# M843E.net
KiCad netlist of a schematic drawn in EAGLE
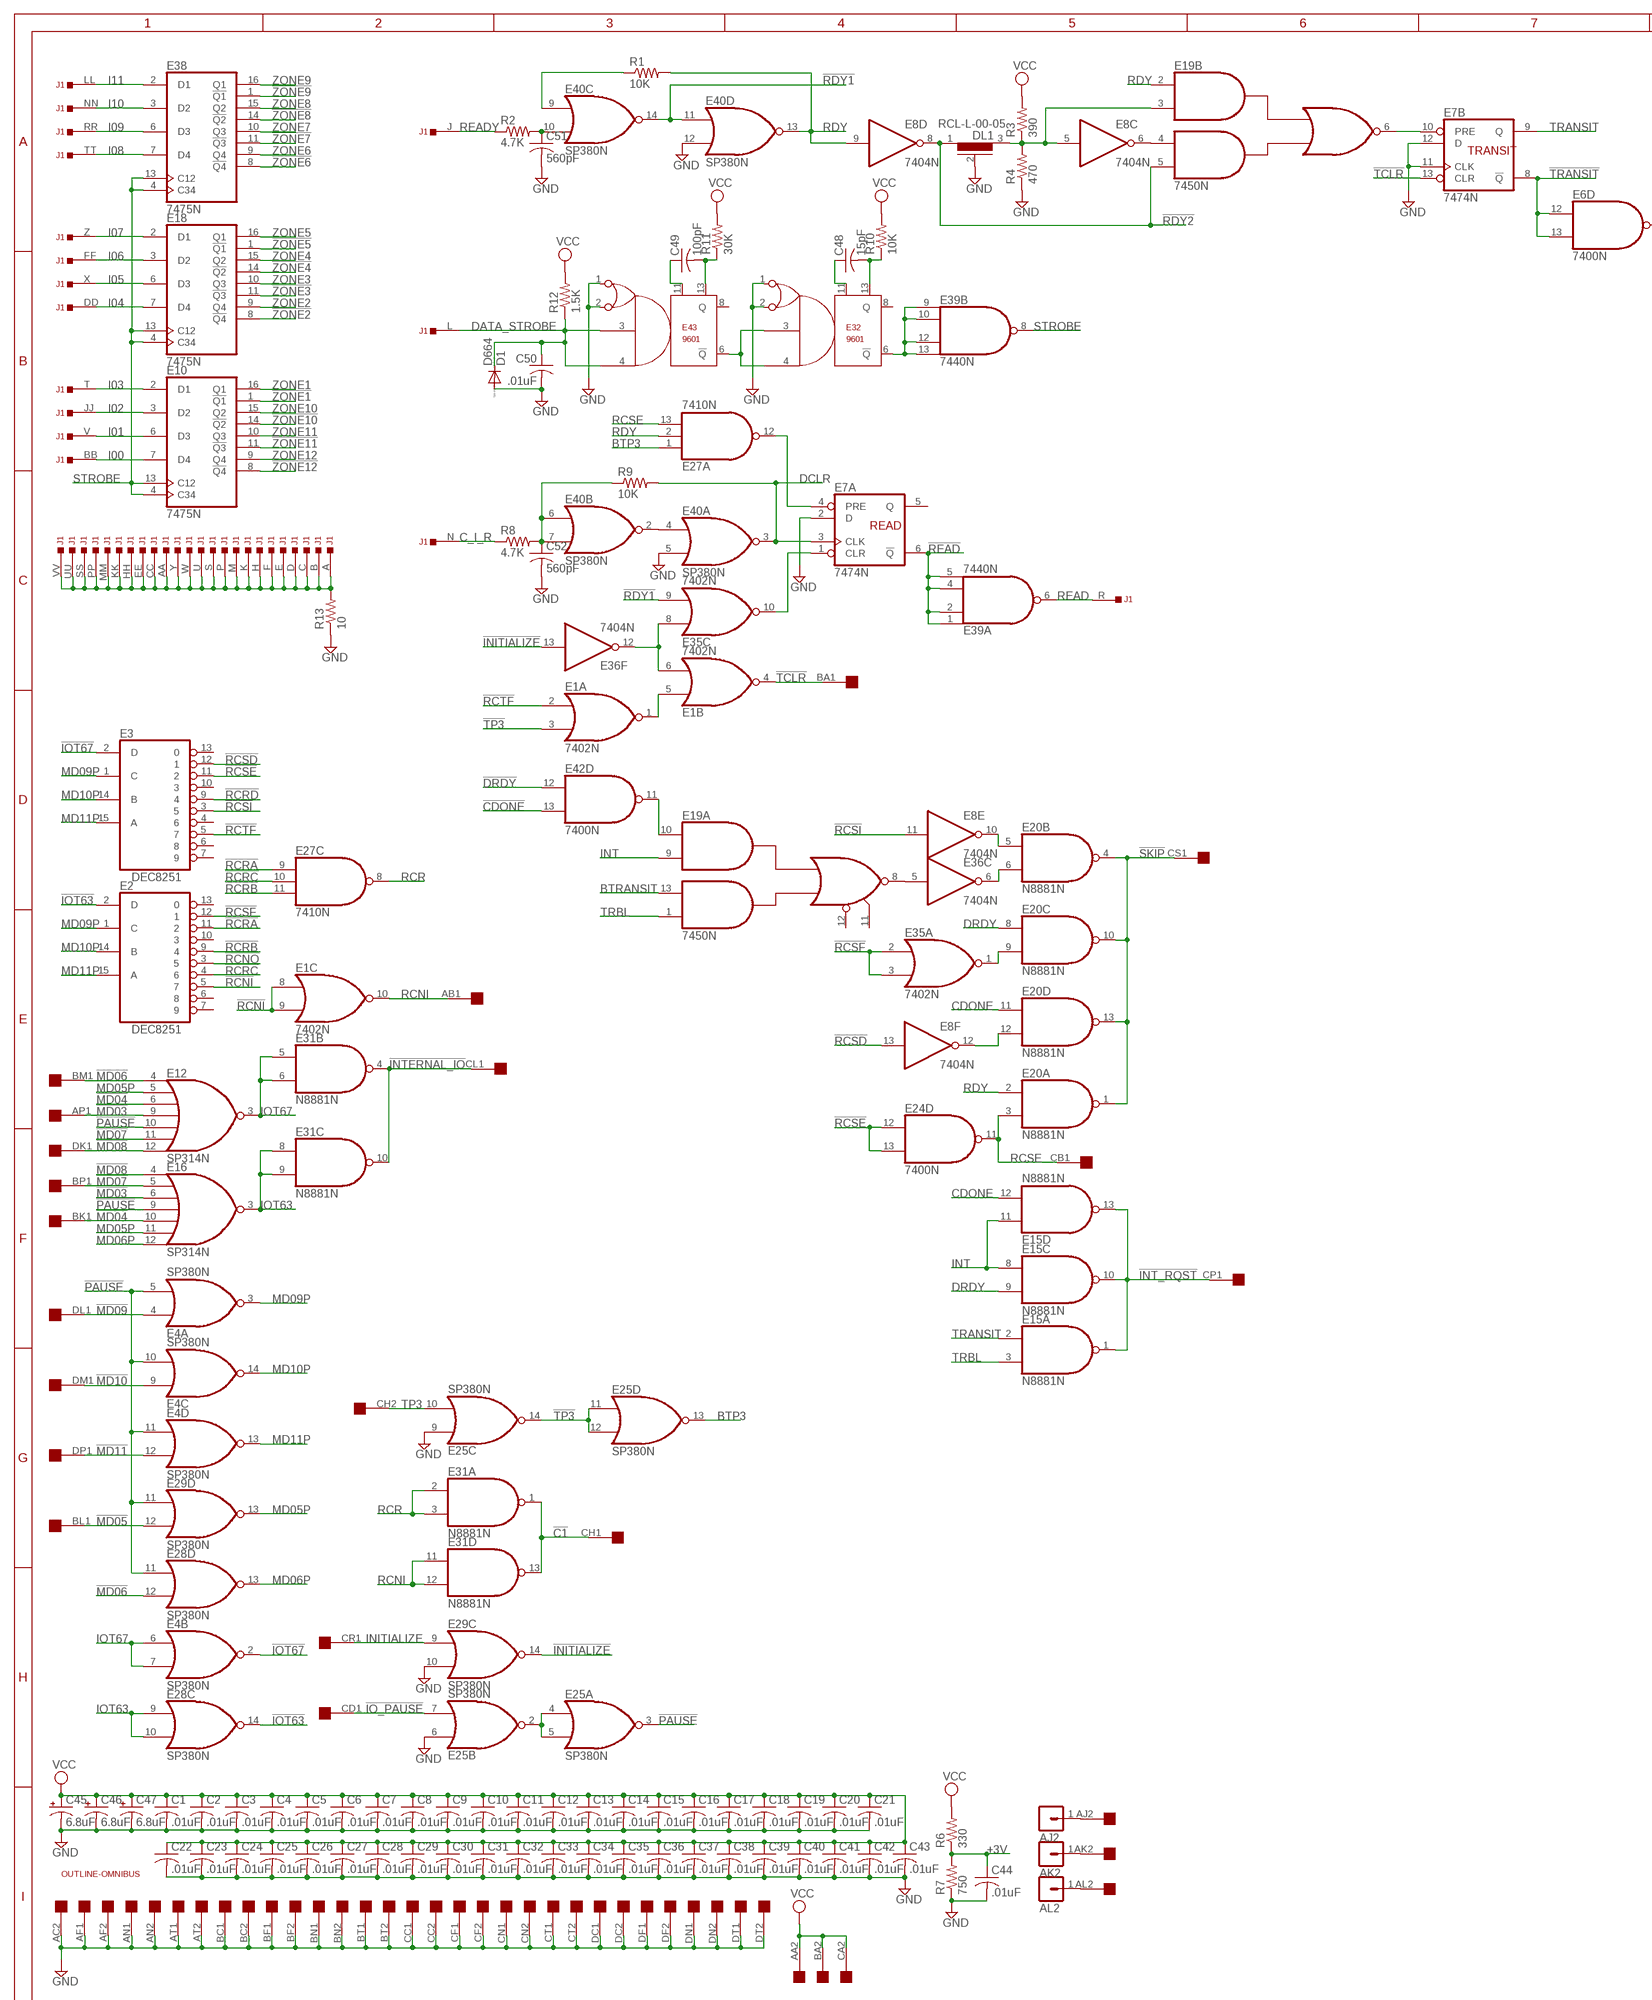
[diagram p0: schematic, sheet 1, part 1 of 2]
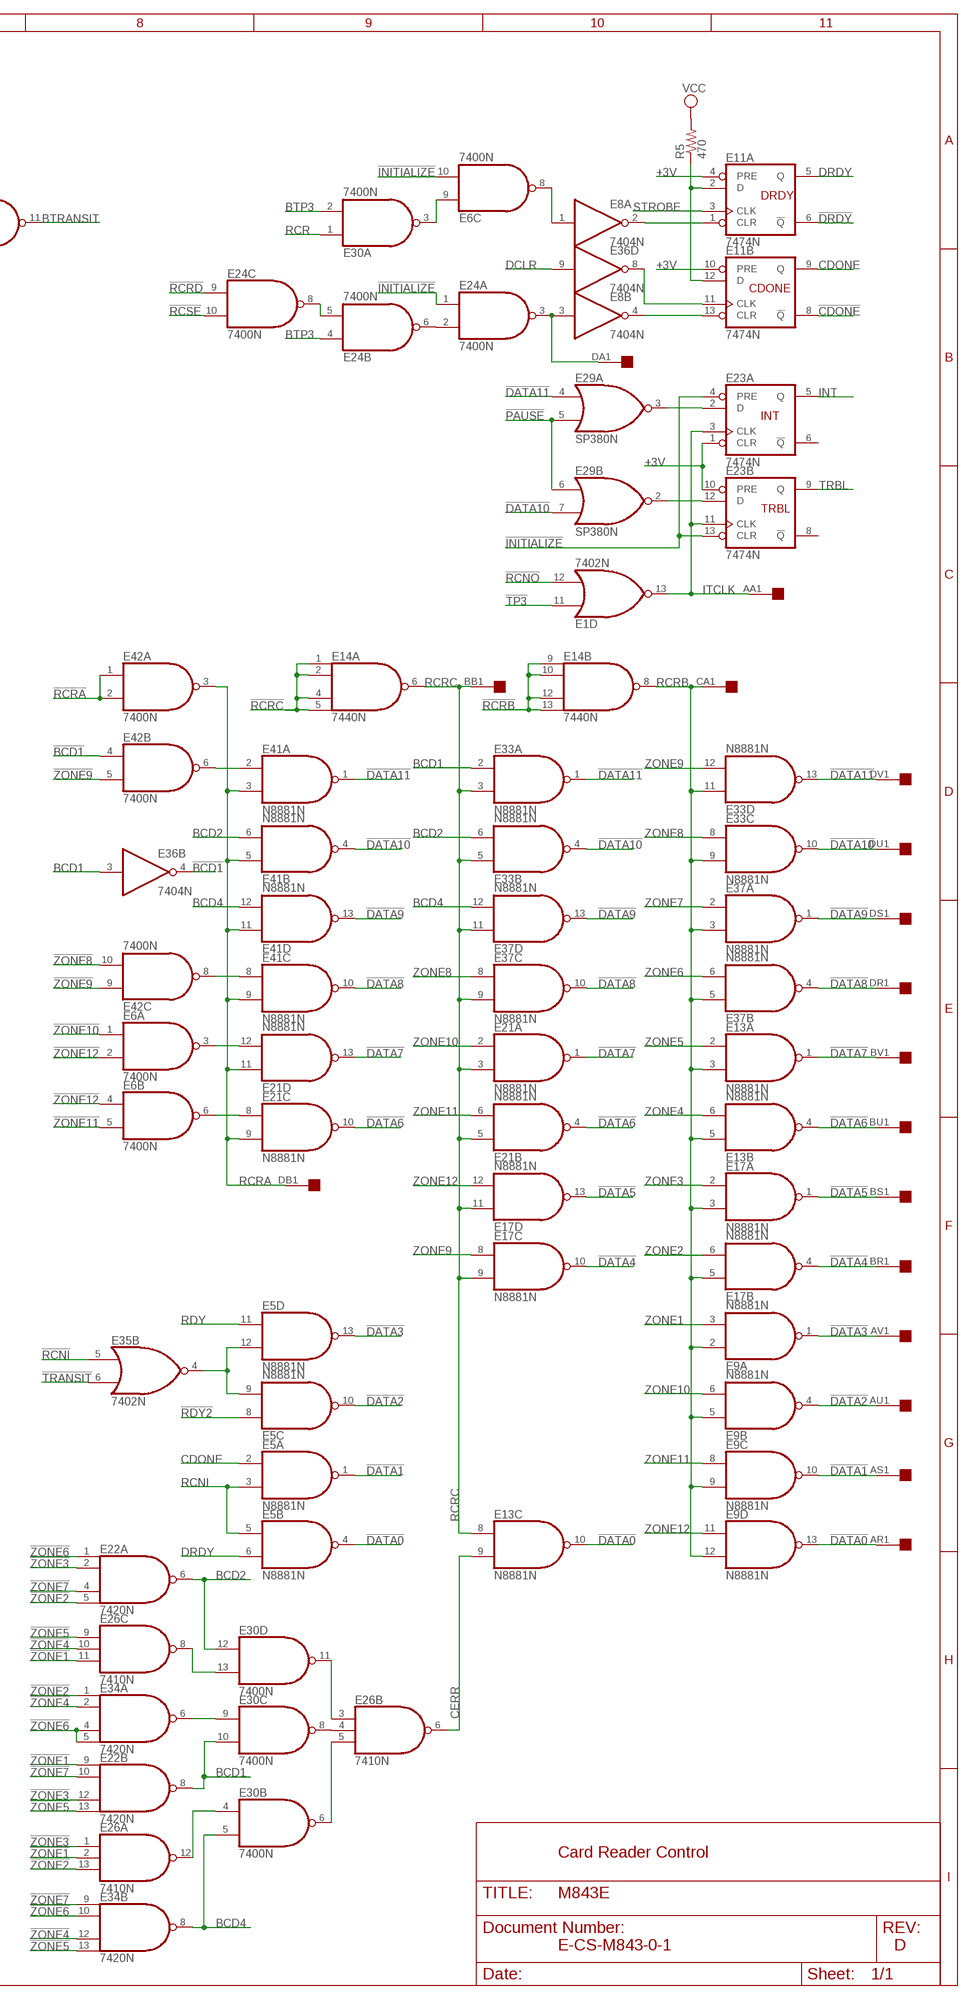
[diagram p1: schematic, sheet 1, part 2 of 2]

(export (version "E")
  (design (tool "Eeschema 10.0.6"))
  (components
    (comp (ref "AJ2")
      (value "MA01-1")
      (footprint "eagle-import:MA01-1")
      (libsource (lib "eagle-import") (part "MA01-1"))
    )
    (comp (ref "AK2")
      (value "MA01-1")
      (footprint "eagle-import:MA01-1")
      (libsource (lib "eagle-import") (part "MA01-1"))
    )
    (comp (ref "AL2")
      (value "MA01-1")
      (footprint "eagle-import:MA01-1")
      (libsource (lib "eagle-import") (part "MA01-1"))
    )
    (comp (ref "C1")
      (value ".01uF")
      (footprint "eagle-import:C075-032X103")
      (libsource (lib "eagle-import") (part "C-US075-032X103"))
    )
    (comp (ref "C2")
      (value ".01uF")
      (footprint "eagle-import:C063-025X075")
      (libsource (lib "eagle-import") (part "C-US"))
    )
    (comp (ref "C3")
      (value ".01uF")
      (footprint "eagle-import:C063-025X075")
      (libsource (lib "eagle-import") (part "C-US"))
    )
    (comp (ref "C4")
      (value ".01uF")
      (footprint "eagle-import:C063-025X075")
      (libsource (lib "eagle-import") (part "C-US"))
    )
    (comp (ref "C5")
      (value ".01uF")
      (footprint "eagle-import:C063-025X075")
      (libsource (lib "eagle-import") (part "C-US"))
    )
    (comp (ref "C6")
      (value ".01uF")
      (footprint "eagle-import:C075-032X103")
      (libsource (lib "eagle-import") (part "C-US075-032X103"))
    )
    (comp (ref "C7")
      (value ".01uF")
      (footprint "eagle-import:C063-025X075")
      (libsource (lib "eagle-import") (part "C-US"))
    )
    (comp (ref "C8")
      (value ".01uF")
      (footprint "eagle-import:C063-025X075")
      (libsource (lib "eagle-import") (part "C-US"))
    )
    (comp (ref "C9")
      (value ".01uF")
      (footprint "eagle-import:C063-025X075")
      (libsource (lib "eagle-import") (part "C-US"))
    )
    (comp (ref "C10")
      (value ".01uF")
      (footprint "eagle-import:C063-025X075")
      (libsource (lib "eagle-import") (part "C-US"))
    )
    (comp (ref "C11")
      (value ".01uF")
      (footprint "eagle-import:C063-025X075")
      (libsource (lib "eagle-import") (part "C-US"))
    )
    (comp (ref "C12")
      (value ".01uF")
      (footprint "eagle-import:C063-025X075")
      (libsource (lib "eagle-import") (part "C-US"))
    )
    (comp (ref "C13")
      (value ".01uF")
      (footprint "eagle-import:C063-025X075")
      (libsource (lib "eagle-import") (part "C-US"))
    )
    (comp (ref "C14")
      (value ".01uF")
      (footprint "eagle-import:C063-025X075")
      (libsource (lib "eagle-import") (part "C-US"))
    )
    (comp (ref "C15")
      (value ".01uF")
      (footprint "eagle-import:C063-025X075")
      (libsource (lib "eagle-import") (part "C-US"))
    )
    (comp (ref "C16")
      (value ".01uF")
      (footprint "eagle-import:C063-025X075")
      (libsource (lib "eagle-import") (part "C-US"))
    )
    (comp (ref "C17")
      (value ".01uF")
      (footprint "eagle-import:C063-025X075")
      (libsource (lib "eagle-import") (part "C-US"))
    )
    (comp (ref "C18")
      (value ".01uF")
      (footprint "eagle-import:C063-025X075")
      (libsource (lib "eagle-import") (part "C-US"))
    )
    (comp (ref "C19")
      (value ".01uF")
      (footprint "eagle-import:C063-025X075")
      (libsource (lib "eagle-import") (part "C-US"))
    )
    (comp (ref "C20")
      (value ".01uF")
      (footprint "eagle-import:C063-025X075")
      (libsource (lib "eagle-import") (part "C-US"))
    )
    (comp (ref "C21")
      (value ".01uF")
      (footprint "eagle-import:C063-025X075")
      (libsource (lib "eagle-import") (part "C-US"))
    )
    (comp (ref "C22")
      (value ".01uF")
      (footprint "eagle-import:C063-025X075")
      (libsource (lib "eagle-import") (part "C-US"))
    )
    (comp (ref "C23")
      (value ".01uF")
      (footprint "eagle-import:C063-025X075")
      (libsource (lib "eagle-import") (part "C-US"))
    )
    (comp (ref "C24")
      (value ".01uF")
      (footprint "eagle-import:C063-025X075")
      (libsource (lib "eagle-import") (part "C-US"))
    )
    (comp (ref "C25")
      (value ".01uF")
      (footprint "eagle-import:C063-025X075")
      (libsource (lib "eagle-import") (part "C-US"))
    )
    (comp (ref "C26")
      (value ".01uF")
      (footprint "eagle-import:C063-025X075")
      (libsource (lib "eagle-import") (part "C-US"))
    )
    (comp (ref "C27")
      (value ".01uF")
      (footprint "eagle-import:C063-025X075")
      (libsource (lib "eagle-import") (part "C-US"))
    )
    (comp (ref "C28")
      (value ".01uF")
      (footprint "eagle-import:C063-025X075")
      (libsource (lib "eagle-import") (part "C-US"))
    )
    (comp (ref "C29")
      (value ".01uF")
      (footprint "eagle-import:C063-025X075")
      (libsource (lib "eagle-import") (part "C-US"))
    )
    (comp (ref "C30")
      (value ".01uF")
      (footprint "eagle-import:C063-025X075")
      (libsource (lib "eagle-import") (part "C-US"))
    )
    (comp (ref "C31")
      (value ".01uF")
      (footprint "eagle-import:C063-025X075")
      (libsource (lib "eagle-import") (part "C-US"))
    )
    (comp (ref "C32")
      (value ".01uF")
      (footprint "eagle-import:C063-025X075")
      (libsource (lib "eagle-import") (part "C-US"))
    )
    (comp (ref "C33")
      (value ".01uF")
      (footprint "eagle-import:C063-025X075")
      (libsource (lib "eagle-import") (part "C-US"))
    )
    (comp (ref "C34")
      (value ".01uF")
      (footprint "eagle-import:C063-025X075")
      (libsource (lib "eagle-import") (part "C-US"))
    )
    (comp (ref "C35")
      (value ".01uF")
      (footprint "eagle-import:C063-025X075")
      (libsource (lib "eagle-import") (part "C-US"))
    )
    (comp (ref "C36")
      (value ".01uF")
      (footprint "eagle-import:C063-025X075")
      (libsource (lib "eagle-import") (part "C-US"))
    )
    (comp (ref "C37")
      (value ".01uF")
      (footprint "eagle-import:C063-025X075")
      (libsource (lib "eagle-import") (part "C-US"))
    )
    (comp (ref "C38")
      (value ".01uF")
      (footprint "eagle-import:C063-025X075")
      (libsource (lib "eagle-import") (part "C-US"))
    )
    (comp (ref "C39")
      (value ".01uF")
      (footprint "eagle-import:C063-025X075")
      (libsource (lib "eagle-import") (part "C-US"))
    )
    (comp (ref "C40")
      (value ".01uF")
      (footprint "eagle-import:C063-025X075")
      (libsource (lib "eagle-import") (part "C-US"))
    )
    (comp (ref "C41")
      (value ".01uF")
      (footprint "eagle-import:C063-025X075")
      (libsource (lib "eagle-import") (part "C-US"))
    )
    (comp (ref "C42")
      (value ".01uF")
      (footprint "eagle-import:C063-025X075")
      (libsource (lib "eagle-import") (part "C-US"))
    )
    (comp (ref "C43")
      (value ".01uF")
      (footprint "eagle-import:C063-025X075")
      (libsource (lib "eagle-import") (part "C-US"))
    )
    (comp (ref "C44")
      (value ".01uF")
      (footprint "eagle-import:C063-025X075")
      (libsource (lib "eagle-import") (part "C-US"))
    )
    (comp (ref "C45")
      (value "6.8uF")
      (footprint "eagle-import:E12-8")
      (libsource (lib "eagle-import") (part "CPOL-USE20-8AXIAL"))
    )
    (comp (ref "C46")
      (value "6.8uF")
      (footprint "eagle-import:E12-8")
      (libsource (lib "eagle-import") (part "CPOL-USE20-8AXIAL"))
    )
    (comp (ref "C47")
      (value "6.8uF")
      (footprint "eagle-import:E12-8")
      (libsource (lib "eagle-import") (part "CPOL-USE20-8AXIAL"))
    )
    (comp (ref "C48")
      (value "15pF")
      (footprint "eagle-import:C075-032X103")
      (libsource (lib "eagle-import") (part "C-US075-032X103"))
    )
    (comp (ref "C49")
      (value "100pF")
      (footprint "eagle-import:C075-032X103")
      (libsource (lib "eagle-import") (part "C-US075-032X103"))
    )
    (comp (ref "C50")
      (value ".01uF")
      (footprint "eagle-import:C063-025X075")
      (libsource (lib "eagle-import") (part "C-US"))
    )
    (comp (ref "C51")
      (value "560pF")
      (footprint "eagle-import:C075-032X103")
      (libsource (lib "eagle-import") (part "C-US075-032X103"))
    )
    (comp (ref "C52")
      (value "560pF")
      (footprint "eagle-import:C075-032X103")
      (libsource (lib "eagle-import") (part "C-US075-032X103"))
    )
    (comp (ref "D1")
      (value "D664")
      (footprint "eagle-import:DO35-10")
      (libsource (lib "eagle-import") (part "DIODE-DO35-10"))
    )
    (comp (ref "DL1")
      (value "RCL-L-00-05")
      (footprint "eagle-import:RCL-L-00-05")
      (libsource (lib "eagle-import") (part "RCL-L-00-05"))
    )
    (comp (ref "E1")
      (value "7402N")
      (footprint "eagle-import:DIL14")
      (libsource (lib "eagle-import") (part "7402N"))
    )
    (comp (ref "E2")
      (value "DEC8251")
      (footprint "eagle-import:DIL16")
      (libsource (lib "eagle-import") (part "DEC8251"))
    )
    (comp (ref "E3")
      (value "DEC8251")
      (footprint "eagle-import:DIL16")
      (libsource (lib "eagle-import") (part "DEC8251"))
    )
    (comp (ref "E4")
      (value "SP380N")
      (footprint "eagle-import:DIL14")
      (libsource (lib "eagle-import") (part "SP380N"))
    )
    (comp (ref "E5")
      (value "N8881N")
      (footprint "eagle-import:DIL14")
      (libsource (lib "eagle-import") (part "N8881N"))
    )
    (comp (ref "E6")
      (value "7400N")
      (footprint "eagle-import:DIL14")
      (libsource (lib "eagle-import") (part "7400N"))
    )
    (comp (ref "E7")
      (value "7474N")
      (footprint "eagle-import:DIL14")
      (libsource (lib "eagle-import") (part "7474NS"))
    )
    (comp (ref "E8")
      (value "7404N")
      (footprint "eagle-import:DIL14")
      (libsource (lib "eagle-import") (part "7404N"))
    )
    (comp (ref "E9")
      (value "N8881N")
      (footprint "eagle-import:DIL14")
      (libsource (lib "eagle-import") (part "N8881N"))
    )
    (comp (ref "E10")
      (value "7475N")
      (footprint "eagle-import:DIL16")
      (libsource (lib "eagle-import") (part "7475N"))
    )
    (comp (ref "E11")
      (value "7474N")
      (footprint "eagle-import:DIL14")
      (libsource (lib "eagle-import") (part "7474NS"))
    )
    (comp (ref "E12")
      (value "SP314N")
      (footprint "eagle-import:DIL14")
      (libsource (lib "eagle-import") (part "SP314N"))
    )
    (comp (ref "E13")
      (value "N8881N")
      (footprint "eagle-import:DIL14")
      (libsource (lib "eagle-import") (part "N8881N"))
    )
    (comp (ref "E14")
      (value "7440N")
      (footprint "eagle-import:DIL14")
      (libsource (lib "eagle-import") (part "7440N"))
    )
    (comp (ref "E15")
      (value "N8881N")
      (footprint "eagle-import:DIL14")
      (libsource (lib "eagle-import") (part "N8881N"))
    )
    (comp (ref "E16")
      (value "SP314N")
      (footprint "eagle-import:DIL14")
      (libsource (lib "eagle-import") (part "SP314N"))
    )
    (comp (ref "E17")
      (value "N8881N")
      (footprint "eagle-import:DIL14")
      (libsource (lib "eagle-import") (part "N8881N"))
    )
    (comp (ref "E18")
      (value "7475N")
      (footprint "eagle-import:DIL16")
      (libsource (lib "eagle-import") (part "7475N"))
    )
    (comp (ref "E19")
      (value "7450N")
      (footprint "eagle-import:DIL14")
      (libsource (lib "eagle-import") (part "7450N"))
    )
    (comp (ref "E20")
      (value "N8881N")
      (footprint "eagle-import:DIL14")
      (libsource (lib "eagle-import") (part "N8881N"))
    )
    (comp (ref "E21")
      (value "N8881N")
      (footprint "eagle-import:DIL14")
      (libsource (lib "eagle-import") (part "N8881N"))
    )
    (comp (ref "E22")
      (value "7420N")
      (footprint "eagle-import:DIL14")
      (libsource (lib "eagle-import") (part "7420N"))
    )
    (comp (ref "E23")
      (value "7474N")
      (footprint "eagle-import:DIL14")
      (libsource (lib "eagle-import") (part "7474NS"))
    )
    (comp (ref "E24")
      (value "7400N")
      (footprint "eagle-import:DIL14")
      (libsource (lib "eagle-import") (part "7400N"))
    )
    (comp (ref "E25")
      (value "SP380N")
      (footprint "eagle-import:DIL14")
      (libsource (lib "eagle-import") (part "SP380N"))
    )
    (comp (ref "E26")
      (value "7410N")
      (footprint "eagle-import:DIL14")
      (libsource (lib "eagle-import") (part "7410N"))
    )
    (comp (ref "E27")
      (value "7410N")
      (footprint "eagle-import:DIL14")
      (libsource (lib "eagle-import") (part "7410N"))
    )
    (comp (ref "E28")
      (value "SP380N")
      (footprint "eagle-import:DIL14")
      (libsource (lib "eagle-import") (part "SP380N"))
    )
    (comp (ref "E29")
      (value "SP380N")
      (footprint "eagle-import:DIL14")
      (libsource (lib "eagle-import") (part "SP380N"))
    )
    (comp (ref "E30")
      (value "7400N")
      (footprint "eagle-import:DIL14")
      (libsource (lib "eagle-import") (part "7400N"))
    )
    (comp (ref "E31")
      (value "N8881N")
      (footprint "eagle-import:DIL14")
      (libsource (lib "eagle-import") (part "N8881N"))
    )
    (comp (ref "E32")
      (value "9601")
      (footprint "eagle-import:DIL14")
      (libsource (lib "eagle-import") (part "9601"))
    )
    (comp (ref "E33")
      (value "N8881N")
      (footprint "eagle-import:DIL14")
      (libsource (lib "eagle-import") (part "N8881N"))
    )
    (comp (ref "E34")
      (value "7420N")
      (footprint "eagle-import:DIL14")
      (libsource (lib "eagle-import") (part "7420N"))
    )
    (comp (ref "E35")
      (value "7402N")
      (footprint "eagle-import:DIL14")
      (libsource (lib "eagle-import") (part "7402N"))
    )
    (comp (ref "E36")
      (value "7404N")
      (footprint "eagle-import:DIL14")
      (libsource (lib "eagle-import") (part "7404N"))
    )
    (comp (ref "E37")
      (value "N8881N")
      (footprint "eagle-import:DIL14")
      (libsource (lib "eagle-import") (part "N8881N"))
    )
    (comp (ref "E38")
      (value "7475N")
      (footprint "eagle-import:DIL16")
      (libsource (lib "eagle-import") (part "7475N"))
    )
    (comp (ref "E39")
      (value "7440N")
      (footprint "eagle-import:DIL14")
      (libsource (lib "eagle-import") (part "7440N"))
    )
    (comp (ref "E40")
      (value "SP380N")
      (footprint "eagle-import:DIL14")
      (libsource (lib "eagle-import") (part "SP380N"))
    )
    (comp (ref "E41")
      (value "N8881N")
      (footprint "eagle-import:DIL14")
      (libsource (lib "eagle-import") (part "N8881N"))
    )
    (comp (ref "E42")
      (value "7400N")
      (footprint "eagle-import:DIL14")
      (libsource (lib "eagle-import") (part "7400N"))
    )
    (comp (ref "E43")
      (value "9601")
      (footprint "eagle-import:DIL14")
      (libsource (lib "eagle-import") (part "9601"))
    )
    (comp (ref "EDGE")
      (value "OMNIBUS")
      (footprint "eagle-import:EDGE-CON8")
      (libsource (lib "eagle-import") (part "QUAD"))
    )
    (comp (ref "J1")
      (value "DEC40PINSH")
      (footprint "eagle-import:DEC40PINH")
      (libsource (lib "eagle-import") (part "DEC40PINSH"))
    )
    (comp (ref "R1")
      (value "10K")
      (footprint "eagle-import:0207_10")
      (libsource (lib "eagle-import") (part "R-US_0207/10"))
    )
    (comp (ref "R2")
      (value "4.7K")
      (footprint "eagle-import:0207_10")
      (libsource (lib "eagle-import") (part "R-US_0207/10"))
    )
    (comp (ref "R3")
      (value "390")
      (footprint "eagle-import:0207_10")
      (libsource (lib "eagle-import") (part "R-US_0207/10"))
    )
    (comp (ref "R4")
      (value "470")
      (footprint "eagle-import:0207_10")
      (libsource (lib "eagle-import") (part "R-US_0207/10"))
    )
    (comp (ref "R5")
      (value "470")
      (footprint "eagle-import:0207_10")
      (libsource (lib "eagle-import") (part "R-US_0207/10"))
    )
    (comp (ref "R6")
      (value "330")
      (footprint "eagle-import:0207_10")
      (libsource (lib "eagle-import") (part "R-US_0207/10"))
    )
    (comp (ref "R7")
      (value "750")
      (footprint "eagle-import:0207_10")
      (libsource (lib "eagle-import") (part "R-US_0207/10"))
    )
    (comp (ref "R8")
      (value "4.7K")
      (footprint "eagle-import:0207_10")
      (libsource (lib "eagle-import") (part "R-US_0207/10"))
    )
    (comp (ref "R9")
      (value "10K")
      (footprint "eagle-import:0207_10")
      (libsource (lib "eagle-import") (part "R-US_0207/10"))
    )
    (comp (ref "R10")
      (value "10K")
      (footprint "eagle-import:0207_10")
      (libsource (lib "eagle-import") (part "R-US_0207/10"))
    )
    (comp (ref "R11")
      (value "30K")
      (footprint "eagle-import:0207_10")
      (libsource (lib "eagle-import") (part "R-US_0207/10"))
    )
    (comp (ref "R12")
      (value "1.5K")
      (footprint "eagle-import:0207_10")
      (libsource (lib "eagle-import") (part "R-US_0207/10"))
    )
    (comp (ref "R13")
      (value "10")
      (footprint "eagle-import:0207_10")
      (libsource (lib "eagle-import") (part "R-US_0207/10"))
    )
    (comp (ref "U$4")
      (value "OUTLINE-OMNIBUS")
      (footprint "eagle-import:OMNIBUS")
      (libsource (lib "eagle-import") (part "OUTLINE-OMNIBUS"))
    )
  )
  (nets
    (net (code "1") (name "/+3V") (class "Default")
      (node (ref "C44") (pin "1") (pinfunction "1_1") (pintype "passive"))
      (node (ref "E11") (pin "10") (pinfunction "PRE_10") (pintype "input"))
      (node (ref "E11") (pin "4") (pinfunction "PRE_4") (pintype "input"))
      (node (ref "E23") (pin "1") (pinfunction "CLR_1") (pintype "input"))
      (node (ref "E23") (pin "10") (pinfunction "PRE_10") (pintype "input"))
      (node (ref "R6") (pin "1") (pinfunction "1_1") (pintype "passive"))
      (node (ref "R7") (pin "2") (pinfunction "2_2") (pintype "passive"))
    )
    (net (code "2") (name "/BCD1") (class "Default")
      (node (ref "E22") (pin "8") (pinfunction "O_8") (pintype "output"))
      (node (ref "E30") (pin "10") (pinfunction "I1_10") (pintype "input"))
      (node (ref "E33") (pin "2") (pinfunction "I0_2") (pintype "input"))
      (node (ref "E36") (pin "3") (pinfunction "I_3") (pintype "input"))
    )
    (net (code "3") (name "/BCD2") (class "Default")
      (node (ref "E22") (pin "6") (pinfunction "O_6") (pintype "output"))
      (node (ref "E30") (pin "12") (pinfunction "I0_12") (pintype "input"))
      (node (ref "E33") (pin "6") (pinfunction "I1_6") (pintype "input"))
      (node (ref "E41") (pin "6") (pinfunction "I1_6") (pintype "input"))
    )
    (net (code "4") (name "/BCD4") (class "Default")
      (node (ref "E30") (pin "5") (pinfunction "I1_5") (pintype "input"))
      (node (ref "E34") (pin "8") (pinfunction "O_8") (pintype "output"))
      (node (ref "E37") (pin "12") (pinfunction "I1_12") (pintype "input"))
      (node (ref "E41") (pin "12") (pinfunction "I1_12") (pintype "input"))
    )
    (net (code "5") (name "/BTP3") (class "Default")
      (node (ref "E24") (pin "4") (pinfunction "I0_4") (pintype "input"))
      (node (ref "E25") (pin "13") (pinfunction "O_13") (pintype "output"))
      (node (ref "E27") (pin "1") (pinfunction "I0_1") (pintype "input"))
      (node (ref "E30") (pin "2") (pinfunction "I1_2") (pintype "input"))
    )
    (net (code "6") (name "/BTRANSIT") (class "Default")
      (node (ref "E19") (pin "13") (pinfunction "I3_13") (pintype "input"))
      (node (ref "E6") (pin "11") (pinfunction "O_11") (pintype "output"))
    )
    (net (code "7") (name "/CDONE") (class "Default")
      (node (ref "E11") (pin "9") (pinfunction "Q_9") (pintype "output"))
      (node (ref "E15") (pin "12") (pinfunction "I1_12") (pintype "input"))
      (node (ref "E20") (pin "11") (pinfunction "I0_11") (pintype "input"))
      (node (ref "E5") (pin "2") (pinfunction "I0_2") (pintype "input"))
    )
    (net (code "8") (name "/CERR") (class "Default")
      (node (ref "E13") (pin "9") (pinfunction "I1_9") (pintype "input"))
      (node (ref "E26") (pin "6") (pinfunction "O_6") (pintype "output"))
    )
    (net (code "9") (name "/C_I_R") (class "Default")
      (node (ref "J1") (pin "N") (pinfunction "P_N") (pintype "passive"))
      (node (ref "R8") (pin "1") (pinfunction "1_1") (pintype "passive"))
    )
    (net (code "10") (name "/DATA_STROBE") (class "Default")
      (node (ref "C50") (pin "1") (pinfunction "1_1") (pintype "passive"))
      (node (ref "D1") (pin "C") (pinfunction "C_C") (pintype "passive"))
      (node (ref "E43") (pin "3") (pinfunction "P$3_3") (pintype "input"))
      (node (ref "E43") (pin "4") (pinfunction "P$4_4") (pintype "input"))
      (node (ref "J1") (pin "L") (pinfunction "P_L") (pintype "passive"))
      (node (ref "R12") (pin "1") (pinfunction "1_1") (pintype "passive"))
    )
    (net (code "11") (name "/DCLR") (class "Default")
      (node (ref "E36") (pin "9") (pinfunction "I_9") (pintype "input"))
      (node (ref "E40") (pin "3") (pinfunction "O_3") (pintype "output"))
      (node (ref "E7") (pin "3") (pinfunction "CLK_3") (pintype "input"))
      (node (ref "R9") (pin "2") (pinfunction "2_2") (pintype "passive"))
    )
    (net (code "12") (name "/DRDY") (class "Default")
      (node (ref "E11") (pin "5") (pinfunction "Q_5") (pintype "output"))
      (node (ref "E15") (pin "9") (pinfunction "I1_9") (pintype "input"))
      (node (ref "E20") (pin "8") (pinfunction "I0_8") (pintype "input"))
      (node (ref "E5") (pin "6") (pinfunction "I1_6") (pintype "input"))
    )
    (net (code "13") (name "/I00") (class "Default")
      (node (ref "E10") (pin "7") (pinfunction "D4_7") (pintype "input"))
      (node (ref "J1") (pin "BB") (pinfunction "P_BB") (pintype "passive"))
    )
    (net (code "14") (name "/I01") (class "Default")
      (node (ref "E10") (pin "6") (pinfunction "D3_6") (pintype "input"))
      (node (ref "J1") (pin "V") (pinfunction "P_V") (pintype "passive"))
    )
    (net (code "15") (name "/I02") (class "Default")
      (node (ref "E10") (pin "3") (pinfunction "D2_3") (pintype "input"))
      (node (ref "J1") (pin "JJ") (pinfunction "P_JJ") (pintype "passive"))
    )
    (net (code "16") (name "/I03") (class "Default")
      (node (ref "E10") (pin "2") (pinfunction "D1_2") (pintype "input"))
      (node (ref "J1") (pin "T") (pinfunction "P_T") (pintype "passive"))
    )
    (net (code "17") (name "/I04") (class "Default")
      (node (ref "E18") (pin "7") (pinfunction "D4_7") (pintype "input"))
      (node (ref "J1") (pin "DD") (pinfunction "P_DD") (pintype "passive"))
    )
    (net (code "18") (name "/I05") (class "Default")
      (node (ref "E18") (pin "6") (pinfunction "D3_6") (pintype "input"))
      (node (ref "J1") (pin "X") (pinfunction "P_X") (pintype "passive"))
    )
    (net (code "19") (name "/I06") (class "Default")
      (node (ref "E18") (pin "3") (pinfunction "D2_3") (pintype "input"))
      (node (ref "J1") (pin "FF") (pinfunction "P_FF") (pintype "passive"))
    )
    (net (code "20") (name "/I07") (class "Default")
      (node (ref "E18") (pin "2") (pinfunction "D1_2") (pintype "input"))
      (node (ref "J1") (pin "Z") (pinfunction "P_Z") (pintype "passive"))
    )
    (net (code "21") (name "/I08") (class "Default")
      (node (ref "E38") (pin "7") (pinfunction "D4_7") (pintype "input"))
      (node (ref "J1") (pin "TT") (pinfunction "P_TT") (pintype "passive"))
    )
    (net (code "22") (name "/I09") (class "Default")
      (node (ref "E38") (pin "6") (pinfunction "D3_6") (pintype "input"))
      (node (ref "J1") (pin "RR") (pinfunction "P_RR") (pintype "passive"))
    )
    (net (code "23") (name "/I10") (class "Default")
      (node (ref "E38") (pin "3") (pinfunction "D2_3") (pintype "input"))
      (node (ref "J1") (pin "NN") (pinfunction "P_NN") (pintype "passive"))
    )
    (net (code "24") (name "/I11") (class "Default")
      (node (ref "E38") (pin "2") (pinfunction "D1_2") (pintype "input"))
      (node (ref "J1") (pin "LL") (pinfunction "P_LL") (pintype "passive"))
    )
    (net (code "25") (name "/INITIALIZE") (class "Default")
      (node (ref "E29") (pin "9") (pinfunction "I0_9") (pintype "input"))
      (node (ref "EDGE") (pin "CR1") (pinfunction "1_CR1") (pintype "bidirectional"))
    )
    (net (code "26") (name "/INT") (class "Default")
      (node (ref "E15") (pin "11") (pinfunction "I0_11") (pintype "input"))
      (node (ref "E15") (pin "8") (pinfunction "I0_8") (pintype "input"))
      (node (ref "E19") (pin "9") (pinfunction "I2_9") (pintype "input"))
      (node (ref "E23") (pin "5") (pinfunction "Q_5") (pintype "output"))
    )
    (net (code "27") (name "/IOT63") (class "Default")
      (node (ref "E16") (pin "3") (pinfunction "O_3") (pintype "output"))
      (node (ref "E28") (pin "10") (pinfunction "I1_10") (pintype "input"))
      (node (ref "E28") (pin "9") (pinfunction "I0_9") (pintype "input"))
      (node (ref "E31") (pin "8") (pinfunction "I0_8") (pintype "input"))
      (node (ref "E31") (pin "9") (pinfunction "I1_9") (pintype "input"))
    )
    (net (code "28") (name "/IOT67") (class "Default")
      (node (ref "E12") (pin "3") (pinfunction "O_3") (pintype "output"))
      (node (ref "E31") (pin "5") (pinfunction "I0_5") (pintype "input"))
      (node (ref "E31") (pin "6") (pinfunction "I1_6") (pintype "input"))
      (node (ref "E4") (pin "6") (pinfunction "I0_6") (pintype "input"))
      (node (ref "E4") (pin "7") (pinfunction "I1_7") (pintype "input"))
    )
    (net (code "29") (name "/ITCLK") (class "Default")
      (node (ref "E1") (pin "13") (pinfunction "O_13") (pintype "output"))
      (node (ref "E23") (pin "11") (pinfunction "CLK_11") (pintype "input"))
      (node (ref "E23") (pin "3") (pinfunction "CLK_3") (pintype "input"))
      (node (ref "EDGE") (pin "AA1") (pinfunction "1_AA1") (pintype "bidirectional"))
    )
    (net (code "30") (name "/MD05P") (class "Default")
      (node (ref "E12") (pin "5") (pinfunction "I1_5") (pintype "input"))
      (node (ref "E16") (pin "11") (pinfunction "I5_11") (pintype "input"))
      (node (ref "E29") (pin "13") (pinfunction "O_13") (pintype "output"))
    )
    (net (code "31") (name "/MD06P") (class "Default")
      (node (ref "E16") (pin "12") (pinfunction "I6_12") (pintype "input"))
      (node (ref "E28") (pin "13") (pinfunction "O_13") (pintype "output"))
    )
    (net (code "32") (name "/MD09P") (class "Default")
      (node (ref "E2") (pin "1") (pinfunction "C_1") (pintype "input"))
      (node (ref "E3") (pin "1") (pinfunction "C_1") (pintype "input"))
      (node (ref "E4") (pin "3") (pinfunction "O_3") (pintype "output"))
    )
    (net (code "33") (name "/MD10P") (class "Default")
      (node (ref "E2") (pin "14") (pinfunction "B_14") (pintype "input"))
      (node (ref "E3") (pin "14") (pinfunction "B_14") (pintype "input"))
      (node (ref "E4") (pin "14") (pinfunction "O_14") (pintype "output"))
    )
    (net (code "34") (name "/MD11P") (class "Default")
      (node (ref "E2") (pin "15") (pinfunction "A_15") (pintype "input"))
      (node (ref "E3") (pin "15") (pinfunction "A_15") (pintype "input"))
      (node (ref "E4") (pin "13") (pinfunction "O_13") (pintype "output"))
    )
    (net (code "35") (name "/RCNI") (class "Default")
      (node (ref "E1") (pin "10") (pinfunction "O_10") (pintype "output"))
      (node (ref "E31") (pin "11") (pinfunction "I0_11") (pintype "input"))
      (node (ref "E31") (pin "12") (pinfunction "I1_12") (pintype "input"))
      (node (ref "E5") (pin "3") (pinfunction "I1_3") (pintype "input"))
      (node (ref "E5") (pin "5") (pinfunction "I0_5") (pintype "input"))
      (node (ref "EDGE") (pin "AB1") (pinfunction "1_AB1") (pintype "bidirectional"))
    )
    (net (code "36") (name "/RCR") (class "Default")
      (node (ref "E27") (pin "8") (pinfunction "O_8") (pintype "output"))
      (node (ref "E30") (pin "1") (pinfunction "I0_1") (pintype "input"))
      (node (ref "E31") (pin "2") (pinfunction "I0_2") (pintype "input"))
      (node (ref "E31") (pin "3") (pinfunction "I1_3") (pintype "input"))
    )
    (net (code "37") (name "/RCRA") (class "Default")
      (node (ref "E21") (pin "11") (pinfunction "I0_11") (pintype "input"))
      (node (ref "E21") (pin "9") (pinfunction "I1_9") (pintype "input"))
      (node (ref "E41") (pin "11") (pinfunction "I0_11") (pintype "input"))
      (node (ref "E41") (pin "3") (pinfunction "I1_3") (pintype "input"))
      (node (ref "E41") (pin "5") (pinfunction "I0_5") (pintype "input"))
      (node (ref "E41") (pin "9") (pinfunction "I1_9") (pintype "input"))
      (node (ref "E42") (pin "3") (pinfunction "O_3") (pintype "output"))
      (node (ref "EDGE") (pin "DB1") (pinfunction "1_DB1") (pintype "bidirectional"))
    )
    (net (code "38") (name "/RCRB") (class "Default")
      (node (ref "E13") (pin "3") (pinfunction "I1_3") (pintype "input"))
      (node (ref "E13") (pin "5") (pinfunction "I0_5") (pintype "input"))
      (node (ref "E14") (pin "8") (pinfunction "O_8") (pintype "output"))
      (node (ref "E17") (pin "3") (pinfunction "I1_3") (pintype "input"))
      (node (ref "E17") (pin "5") (pinfunction "I0_5") (pintype "input"))
      (node (ref "E33") (pin "11") (pinfunction "I0_11") (pintype "input"))
      (node (ref "E33") (pin "9") (pinfunction "I1_9") (pintype "input"))
      (node (ref "E37") (pin "3") (pinfunction "I1_3") (pintype "input"))
      (node (ref "E37") (pin "5") (pinfunction "I0_5") (pintype "input"))
      (node (ref "E9") (pin "12") (pinfunction "I1_12") (pintype "input"))
      (node (ref "E9") (pin "2") (pinfunction "I0_2") (pintype "input"))
      (node (ref "E9") (pin "5") (pinfunction "I0_5") (pintype "input"))
      (node (ref "E9") (pin "9") (pinfunction "I1_9") (pintype "input"))
      (node (ref "EDGE") (pin "CA1") (pinfunction "1_CA1") (pintype "bidirectional"))
    )
    (net (code "39") (name "/RCRC") (class "Default")
      (node (ref "E13") (pin "8") (pinfunction "I0_8") (pintype "input"))
      (node (ref "E14") (pin "6") (pinfunction "O_6") (pintype "output"))
      (node (ref "E17") (pin "11") (pinfunction "I0_11") (pintype "input"))
      (node (ref "E17") (pin "9") (pinfunction "I1_9") (pintype "input"))
      (node (ref "E21") (pin "3") (pinfunction "I1_3") (pintype "input"))
      (node (ref "E21") (pin "5") (pinfunction "I0_5") (pintype "input"))
      (node (ref "E33") (pin "3") (pinfunction "I1_3") (pintype "input"))
      (node (ref "E33") (pin "5") (pinfunction "I0_5") (pintype "input"))
      (node (ref "E37") (pin "11") (pinfunction "I0_11") (pintype "input"))
      (node (ref "E37") (pin "9") (pinfunction "I1_9") (pintype "input"))
      (node (ref "EDGE") (pin "BB1") (pinfunction "1_BB1") (pintype "bidirectional"))
    )
    (net (code "40") (name "/RCSE") (class "Default")
      (node (ref "E20") (pin "3") (pinfunction "I1_3") (pintype "input"))
      (node (ref "E24") (pin "11") (pinfunction "O_11") (pintype "output"))
      (node (ref "E27") (pin "13") (pinfunction "I2_13") (pintype "input"))
      (node (ref "EDGE") (pin "CB1") (pinfunction "1_CB1") (pintype "bidirectional"))
    )
    (net (code "41") (name "/RDY") (class "Default")
      (node (ref "E19") (pin "2") (pinfunction "I1_2") (pintype "input"))
      (node (ref "E20") (pin "2") (pinfunction "I0_2") (pintype "input"))
      (node (ref "E27") (pin "2") (pinfunction "I1_2") (pintype "input"))
      (node (ref "E40") (pin "13") (pinfunction "O_13") (pintype "output"))
      (node (ref "E5") (pin "11") (pinfunction "I0_11") (pintype "input"))
      (node (ref "E8") (pin "9") (pinfunction "I_9") (pintype "input"))
      (node (ref "R1") (pin "2") (pinfunction "2_2") (pintype "passive"))
    )
    (net (code "42") (name "/READ") (class "Default")
      (node (ref "E39") (pin "6") (pinfunction "O_6") (pintype "output"))
      (node (ref "J1") (pin "R") (pinfunction "P_R") (pintype "passive"))
    )
    (net (code "43") (name "/READY") (class "Default")
      (node (ref "J1") (pin "J") (pinfunction "P_J") (pintype "passive"))
      (node (ref "R2") (pin "1") (pinfunction "1_1") (pintype "passive"))
    )
    (net (code "44") (name "/STROBE") (class "Default")
      (node (ref "E10") (pin "13") (pinfunction "C12_13") (pintype "input"))
      (node (ref "E10") (pin "4") (pinfunction "C34_4") (pintype "input"))
      (node (ref "E11") (pin "3") (pinfunction "CLK_3") (pintype "input"))
      (node (ref "E18") (pin "13") (pinfunction "C12_13") (pintype "input"))
      (node (ref "E18") (pin "4") (pinfunction "C34_4") (pintype "input"))
      (node (ref "E38") (pin "13") (pinfunction "C12_13") (pintype "input"))
      (node (ref "E38") (pin "4") (pinfunction "C34_4") (pintype "input"))
      (node (ref "E39") (pin "8") (pinfunction "O_8") (pintype "output"))
    )
    (net (code "45") (name "/TP3") (class "Default")
      (node (ref "E25") (pin "10") (pinfunction "I1_10") (pintype "input"))
      (node (ref "EDGE") (pin "CH2") (pinfunction "1_CH2") (pintype "bidirectional"))
    )
    (net (code "46") (name "/TRANSIT") (class "Default")
      (node (ref "E15") (pin "2") (pinfunction "I0_2") (pintype "input"))
      (node (ref "E7") (pin "9") (pinfunction "Q_9") (pintype "output"))
    )
    (net (code "47") (name "/TRBL") (class "Default")
      (node (ref "E15") (pin "3") (pinfunction "I1_3") (pintype "input"))
      (node (ref "E19") (pin "1") (pinfunction "I4_1") (pintype "input"))
      (node (ref "E23") (pin "9") (pinfunction "Q_9") (pintype "output"))
    )
    (net (code "48") (name "/ZONE1") (class "Default")
      (node (ref "E10") (pin "16") (pinfunction "Q1_16") (pintype "output"))
      (node (ref "E9") (pin "3") (pinfunction "I1_3") (pintype "input"))
    )
    (net (code "49") (name "/ZONE2") (class "Default")
      (node (ref "E17") (pin "6") (pinfunction "I1_6") (pintype "input"))
      (node (ref "E18") (pin "9") (pinfunction "Q4_9") (pintype "output"))
    )
    (net (code "50") (name "/ZONE3") (class "Default")
      (node (ref "E17") (pin "2") (pinfunction "I0_2") (pintype "input"))
      (node (ref "E18") (pin "10") (pinfunction "Q3_10") (pintype "output"))
    )
    (net (code "51") (name "/ZONE4") (class "Default")
      (node (ref "E13") (pin "6") (pinfunction "I1_6") (pintype "input"))
      (node (ref "E18") (pin "15") (pinfunction "Q2_15") (pintype "output"))
    )
    (net (code "52") (name "/ZONE5") (class "Default")
      (node (ref "E13") (pin "2") (pinfunction "I0_2") (pintype "input"))
      (node (ref "E18") (pin "16") (pinfunction "Q1_16") (pintype "output"))
    )
    (net (code "53") (name "/ZONE6") (class "Default")
      (node (ref "E37") (pin "6") (pinfunction "I1_6") (pintype "input"))
      (node (ref "E38") (pin "9") (pinfunction "Q4_9") (pintype "output"))
    )
    (net (code "54") (name "/ZONE7") (class "Default")
      (node (ref "E37") (pin "2") (pinfunction "I0_2") (pintype "input"))
      (node (ref "E38") (pin "10") (pinfunction "Q3_10") (pintype "output"))
    )
    (net (code "55") (name "/ZONE8") (class "Default")
      (node (ref "E33") (pin "8") (pinfunction "I0_8") (pintype "input"))
      (node (ref "E37") (pin "8") (pinfunction "I0_8") (pintype "input"))
      (node (ref "E38") (pin "15") (pinfunction "Q2_15") (pintype "output"))
    )
    (net (code "56") (name "/ZONE9") (class "Default")
      (node (ref "E17") (pin "8") (pinfunction "I0_8") (pintype "input"))
      (node (ref "E33") (pin "12") (pinfunction "I1_12") (pintype "input"))
      (node (ref "E38") (pin "16") (pinfunction "Q1_16") (pintype "output"))
    )
    (net (code "57") (name "/ZONE10") (class "Default")
      (node (ref "E10") (pin "15") (pinfunction "Q2_15") (pintype "output"))
      (node (ref "E21") (pin "2") (pinfunction "I0_2") (pintype "input"))
      (node (ref "E9") (pin "6") (pinfunction "I1_6") (pintype "input"))
    )
    (net (code "58") (name "/ZONE11") (class "Default")
      (node (ref "E10") (pin "10") (pinfunction "Q3_10") (pintype "output"))
      (node (ref "E21") (pin "6") (pinfunction "I1_6") (pintype "input"))
      (node (ref "E9") (pin "8") (pinfunction "I0_8") (pintype "input"))
    )
    (net (code "59") (name "/ZONE12") (class "Default")
      (node (ref "E10") (pin "9") (pinfunction "Q4_9") (pintype "output"))
      (node (ref "E17") (pin "12") (pinfunction "I1_12") (pintype "input"))
      (node (ref "E9") (pin "11") (pinfunction "I0_11") (pintype "input"))
    )
    (net (code "60") (name "/~{BCD1}") (class "Default")
      (node (ref "E36") (pin "4") (pinfunction "O_4") (pintype "output"))
      (node (ref "E42") (pin "4") (pinfunction "I0_4") (pintype "input"))
    )
    (net (code "61") (name "/~{C1}") (class "Default")
      (node (ref "E31") (pin "1") (pinfunction "O_1") (pintype "open_collector"))
      (node (ref "E31") (pin "13") (pinfunction "O_13") (pintype "open_collector"))
      (node (ref "EDGE") (pin "CH1") (pinfunction "1_CH1") (pintype "bidirectional"))
    )
    (net (code "62") (name "/~{CDONE}") (class "Default")
      (node (ref "E11") (pin "8") (pinfunction "~{Q}_8") (pintype "output"))
      (node (ref "E42") (pin "13") (pinfunction "I1_13") (pintype "input"))
    )
    (net (code "63") (name "/~{DATA0}") (class "Default")
      (node (ref "E13") (pin "10") (pinfunction "O_10") (pintype "open_collector"))
      (node (ref "E5") (pin "4") (pinfunction "O_4") (pintype "open_collector"))
      (node (ref "E9") (pin "13") (pinfunction "O_13") (pintype "open_collector"))
      (node (ref "EDGE") (pin "AR1") (pinfunction "1_AR1") (pintype "bidirectional"))
    )
    (net (code "64") (name "/~{DATA1}") (class "Default")
      (node (ref "E5") (pin "1") (pinfunction "O_1") (pintype "open_collector"))
      (node (ref "E9") (pin "10") (pinfunction "O_10") (pintype "open_collector"))
      (node (ref "EDGE") (pin "AS1") (pinfunction "1_AS1") (pintype "bidirectional"))
    )
    (net (code "65") (name "/~{DATA2}") (class "Default")
      (node (ref "E5") (pin "10") (pinfunction "O_10") (pintype "open_collector"))
      (node (ref "E9") (pin "4") (pinfunction "O_4") (pintype "open_collector"))
      (node (ref "EDGE") (pin "AU1") (pinfunction "1_AU1") (pintype "bidirectional"))
    )
    (net (code "66") (name "/~{DATA3}") (class "Default")
      (node (ref "E5") (pin "13") (pinfunction "O_13") (pintype "open_collector"))
      (node (ref "E9") (pin "1") (pinfunction "O_1") (pintype "open_collector"))
      (node (ref "EDGE") (pin "AV1") (pinfunction "1_AV1") (pintype "bidirectional"))
    )
    (net (code "67") (name "/~{DATA4}") (class "Default")
      (node (ref "E17") (pin "10") (pinfunction "O_10") (pintype "open_collector"))
      (node (ref "E17") (pin "4") (pinfunction "O_4") (pintype "open_collector"))
      (node (ref "EDGE") (pin "BR1") (pinfunction "1_BR1") (pintype "bidirectional"))
    )
    (net (code "68") (name "/~{DATA5}") (class "Default")
      (node (ref "E17") (pin "1") (pinfunction "O_1") (pintype "open_collector"))
      (node (ref "E17") (pin "13") (pinfunction "O_13") (pintype "open_collector"))
      (node (ref "EDGE") (pin "BS1") (pinfunction "1_BS1") (pintype "bidirectional"))
    )
    (net (code "69") (name "/~{DATA6}") (class "Default")
      (node (ref "E13") (pin "4") (pinfunction "O_4") (pintype "open_collector"))
      (node (ref "E21") (pin "10") (pinfunction "O_10") (pintype "open_collector"))
      (node (ref "E21") (pin "4") (pinfunction "O_4") (pintype "open_collector"))
      (node (ref "EDGE") (pin "BU1") (pinfunction "1_BU1") (pintype "bidirectional"))
    )
    (net (code "70") (name "/~{DATA7}") (class "Default")
      (node (ref "E13") (pin "1") (pinfunction "O_1") (pintype "open_collector"))
      (node (ref "E21") (pin "1") (pinfunction "O_1") (pintype "open_collector"))
      (node (ref "E21") (pin "13") (pinfunction "O_13") (pintype "open_collector"))
      (node (ref "EDGE") (pin "BV1") (pinfunction "1_BV1") (pintype "bidirectional"))
    )
    (net (code "71") (name "/~{DATA8}") (class "Default")
      (node (ref "E37") (pin "10") (pinfunction "O_10") (pintype "open_collector"))
      (node (ref "E37") (pin "4") (pinfunction "O_4") (pintype "open_collector"))
      (node (ref "E41") (pin "10") (pinfunction "O_10") (pintype "open_collector"))
      (node (ref "EDGE") (pin "DR1") (pinfunction "1_DR1") (pintype "bidirectional"))
    )
    (net (code "72") (name "/~{DATA9}") (class "Default")
      (node (ref "E37") (pin "1") (pinfunction "O_1") (pintype "open_collector"))
      (node (ref "E37") (pin "13") (pinfunction "O_13") (pintype "open_collector"))
      (node (ref "E41") (pin "13") (pinfunction "O_13") (pintype "open_collector"))
      (node (ref "EDGE") (pin "DS1") (pinfunction "1_DS1") (pintype "bidirectional"))
    )
    (net (code "73") (name "/~{DATA10}") (class "Default")
      (node (ref "E29") (pin "7") (pinfunction "I1_7") (pintype "input"))
      (node (ref "E33") (pin "10") (pinfunction "O_10") (pintype "open_collector"))
      (node (ref "E33") (pin "4") (pinfunction "O_4") (pintype "open_collector"))
      (node (ref "E41") (pin "4") (pinfunction "O_4") (pintype "open_collector"))
      (node (ref "EDGE") (pin "DU1") (pinfunction "1_DU1") (pintype "bidirectional"))
    )
    (net (code "74") (name "/~{DATA11}") (class "Default")
      (node (ref "E29") (pin "4") (pinfunction "I0_4") (pintype "input"))
      (node (ref "E33") (pin "1") (pinfunction "O_1") (pintype "open_collector"))
      (node (ref "E33") (pin "13") (pinfunction "O_13") (pintype "open_collector"))
      (node (ref "E41") (pin "1") (pinfunction "O_1") (pintype "open_collector"))
      (node (ref "EDGE") (pin "DV1") (pinfunction "1_DV1") (pintype "bidirectional"))
    )
    (net (code "75") (name "/~{DRDY}") (class "Default")
      (node (ref "E11") (pin "6") (pinfunction "~{Q}_6") (pintype "output"))
      (node (ref "E42") (pin "12") (pinfunction "I0_12") (pintype "input"))
    )
    (net (code "76") (name "/~{INITIALIZE}") (class "Default")
      (node (ref "E23") (pin "13") (pinfunction "CLR_13") (pintype "input"))
      (node (ref "E23") (pin "4") (pinfunction "PRE_4") (pintype "input"))
      (node (ref "E24") (pin "1") (pinfunction "I0_1") (pintype "input"))
      (node (ref "E29") (pin "14") (pinfunction "O_14") (pintype "output"))
      (node (ref "E36") (pin "13") (pinfunction "I_13") (pintype "input"))
      (node (ref "E6") (pin "10") (pinfunction "I1_10") (pintype "input"))
    )
    (net (code "77") (name "/~{INTERNAL_IO}") (class "Default")
      (node (ref "E31") (pin "10") (pinfunction "O_10") (pintype "open_collector"))
      (node (ref "E31") (pin "4") (pinfunction "O_4") (pintype "open_collector"))
      (node (ref "EDGE") (pin "CL1") (pinfunction "1_CL1") (pintype "bidirectional"))
    )
    (net (code "78") (name "/~{INT_RQST}") (class "Default")
      (node (ref "E15") (pin "1") (pinfunction "O_1") (pintype "open_collector"))
      (node (ref "E15") (pin "10") (pinfunction "O_10") (pintype "open_collector"))
      (node (ref "E15") (pin "13") (pinfunction "O_13") (pintype "open_collector"))
      (node (ref "EDGE") (pin "CP1") (pinfunction "1_CP1") (pintype "bidirectional"))
    )
    (net (code "79") (name "/~{IOT63}") (class "Default")
      (node (ref "E2") (pin "2") (pinfunction "D_2") (pintype "input"))
      (node (ref "E28") (pin "14") (pinfunction "O_14") (pintype "output"))
    )
    (net (code "80") (name "/~{IOT67}") (class "Default")
      (node (ref "E3") (pin "2") (pinfunction "D_2") (pintype "input"))
      (node (ref "E4") (pin "2") (pinfunction "O_2") (pintype "output"))
    )
    (net (code "81") (name "/~{IO_PAUSE}") (class "Default")
      (node (ref "E25") (pin "7") (pinfunction "I1_7") (pintype "input"))
      (node (ref "EDGE") (pin "CD1") (pinfunction "1_CD1") (pintype "bidirectional"))
    )
    (net (code "82") (name "/~{MD03}") (class "Default")
      (node (ref "E12") (pin "9") (pinfunction "I3_9") (pintype "input"))
      (node (ref "E16") (pin "6") (pinfunction "I2_6") (pintype "input"))
      (node (ref "EDGE") (pin "AP1") (pinfunction "1_AP1") (pintype "bidirectional"))
    )
    (net (code "83") (name "/~{MD04}") (class "Default")
      (node (ref "E12") (pin "6") (pinfunction "I2_6") (pintype "input"))
      (node (ref "E16") (pin "10") (pinfunction "I4_10") (pintype "input"))
      (node (ref "EDGE") (pin "BK1") (pinfunction "1_BK1") (pintype "bidirectional"))
    )
    (net (code "84") (name "/~{MD05}") (class "Default")
      (node (ref "E29") (pin "12") (pinfunction "I1_12") (pintype "input"))
      (node (ref "EDGE") (pin "BL1") (pinfunction "1_BL1") (pintype "bidirectional"))
    )
    (net (code "85") (name "/~{MD06}") (class "Default")
      (node (ref "E12") (pin "4") (pinfunction "I0_4") (pintype "input"))
      (node (ref "E28") (pin "12") (pinfunction "I1_12") (pintype "input"))
      (node (ref "EDGE") (pin "BM1") (pinfunction "1_BM1") (pintype "bidirectional"))
    )
    (net (code "86") (name "/~{MD07}") (class "Default")
      (node (ref "E12") (pin "11") (pinfunction "I5_11") (pintype "input"))
      (node (ref "E16") (pin "5") (pinfunction "I1_5") (pintype "input"))
      (node (ref "EDGE") (pin "BP1") (pinfunction "1_BP1") (pintype "bidirectional"))
    )
    (net (code "87") (name "/~{MD08}") (class "Default")
      (node (ref "E12") (pin "12") (pinfunction "I6_12") (pintype "input"))
      (node (ref "E16") (pin "4") (pinfunction "I0_4") (pintype "input"))
      (node (ref "EDGE") (pin "DK1") (pinfunction "1_DK1") (pintype "bidirectional"))
    )
    (net (code "88") (name "/~{MD09}") (class "Default")
      (node (ref "E4") (pin "4") (pinfunction "I0_4") (pintype "input"))
      (node (ref "EDGE") (pin "DL1") (pinfunction "1_DL1") (pintype "bidirectional"))
    )
    (net (code "89") (name "/~{MD10}") (class "Default")
      (node (ref "E4") (pin "9") (pinfunction "I0_9") (pintype "input"))
      (node (ref "EDGE") (pin "DM1") (pinfunction "1_DM1") (pintype "bidirectional"))
    )
    (net (code "90") (name "/~{MD11}") (class "Default")
      (node (ref "E4") (pin "12") (pinfunction "I1_12") (pintype "input"))
      (node (ref "EDGE") (pin "DP1") (pinfunction "1_DP1") (pintype "bidirectional"))
    )
    (net (code "91") (name "/~{PAUSE}") (class "Default")
      (node (ref "E12") (pin "10") (pinfunction "I4_10") (pintype "input"))
      (node (ref "E16") (pin "9") (pinfunction "I3_9") (pintype "input"))
      (node (ref "E25") (pin "3") (pinfunction "O_3") (pintype "output"))
      (node (ref "E28") (pin "11") (pinfunction "I0_11") (pintype "input"))
      (node (ref "E29") (pin "11") (pinfunction "I0_11") (pintype "input"))
      (node (ref "E29") (pin "5") (pinfunction "I1_5") (pintype "input"))
      (node (ref "E29") (pin "6") (pinfunction "I0_6") (pintype "input"))
      (node (ref "E4") (pin "10") (pinfunction "I1_10") (pintype "input"))
      (node (ref "E4") (pin "11") (pinfunction "I0_11") (pintype "input"))
      (node (ref "E4") (pin "5") (pinfunction "I1_5") (pintype "input"))
    )
    (net (code "92") (name "/~{RCNI}") (class "Default")
      (node (ref "E1") (pin "8") (pinfunction "I0_8") (pintype "input"))
      (node (ref "E1") (pin "9") (pinfunction "I1_9") (pintype "input"))
      (node (ref "E2") (pin "5") (pinfunction "7_5") (pintype "output"))
      (node (ref "E35") (pin "5") (pinfunction "I0_5") (pintype "input"))
    )
    (net (code "93") (name "/~{RCNO}") (class "Default")
      (node (ref "E1") (pin "12") (pinfunction "I1_12") (pintype "input"))
      (node (ref "E2") (pin "3") (pinfunction "5_3") (pintype "output"))
    )
    (net (code "94") (name "/~{RCRA}") (class "Default")
      (node (ref "E2") (pin "11") (pinfunction "2_11") (pintype "output"))
      (node (ref "E27") (pin "9") (pinfunction "I0_9") (pintype "input"))
      (node (ref "E42") (pin "1") (pinfunction "I0_1") (pintype "input"))
      (node (ref "E42") (pin "2") (pinfunction "I1_2") (pintype "input"))
    )
    (net (code "95") (name "/~{RCRB}") (class "Default")
      (node (ref "E14") (pin "10") (pinfunction "I1_10") (pintype "input"))
      (node (ref "E14") (pin "12") (pinfunction "I2_12") (pintype "input"))
      (node (ref "E14") (pin "13") (pinfunction "I3_13") (pintype "input"))
      (node (ref "E14") (pin "9") (pinfunction "I0_9") (pintype "input"))
      (node (ref "E2") (pin "9") (pinfunction "4_9") (pintype "output"))
      (node (ref "E27") (pin "11") (pinfunction "I2_11") (pintype "input"))
    )
    (net (code "96") (name "/~{RCRC}") (class "Default")
      (node (ref "E14") (pin "1") (pinfunction "I0_1") (pintype "input"))
      (node (ref "E14") (pin "2") (pinfunction "I1_2") (pintype "input"))
      (node (ref "E14") (pin "4") (pinfunction "I2_4") (pintype "input"))
      (node (ref "E14") (pin "5") (pinfunction "I3_5") (pintype "input"))
      (node (ref "E2") (pin "4") (pinfunction "6_4") (pintype "output"))
      (node (ref "E27") (pin "10") (pinfunction "I1_10") (pintype "input"))
    )
    (net (code "97") (name "/~{RCRD}") (class "Default")
      (node (ref "E24") (pin "9") (pinfunction "I0_9") (pintype "input"))
      (node (ref "E3") (pin "9") (pinfunction "4_9") (pintype "output"))
    )
    (net (code "98") (name "/~{RCSD}") (class "Default")
      (node (ref "E3") (pin "12") (pinfunction "1_12") (pintype "output"))
      (node (ref "E8") (pin "13") (pinfunction "I_13") (pintype "input"))
    )
    (net (code "99") (name "/~{RCSE}") (class "Default")
      (node (ref "E24") (pin "10") (pinfunction "I1_10") (pintype "input"))
      (node (ref "E24") (pin "12") (pinfunction "I0_12") (pintype "input"))
      (node (ref "E24") (pin "13") (pinfunction "I1_13") (pintype "input"))
      (node (ref "E3") (pin "11") (pinfunction "2_11") (pintype "output"))
    )
    (net (code "100") (name "/~{RCSF}") (class "Default")
      (node (ref "E2") (pin "12") (pinfunction "1_12") (pintype "output"))
      (node (ref "E35") (pin "2") (pinfunction "I0_2") (pintype "input"))
      (node (ref "E35") (pin "3") (pinfunction "I1_3") (pintype "input"))
    )
    (net (code "101") (name "/~{RCSI}") (class "Default")
      (node (ref "E3") (pin "3") (pinfunction "5_3") (pintype "output"))
      (node (ref "E8") (pin "11") (pinfunction "I_11") (pintype "input"))
    )
    (net (code "102") (name "/~{RCTF}") (class "Default")
      (node (ref "E1") (pin "2") (pinfunction "I0_2") (pintype "input"))
      (node (ref "E3") (pin "5") (pinfunction "7_5") (pintype "output"))
    )
    (net (code "103") (name "/~{RDY1}") (class "Default")
      (node (ref "E35") (pin "9") (pinfunction "I1_9") (pintype "input"))
      (node (ref "E40") (pin "11") (pinfunction "I0_11") (pintype "input"))
      (node (ref "E40") (pin "14") (pinfunction "O_14") (pintype "output"))
    )
    (net (code "104") (name "/~{RDY2}") (class "Default")
      (node (ref "DL1") (pin "1") (pinfunction "1_1") (pintype "passive"))
      (node (ref "E19") (pin "5") (pinfunction "I4_5") (pintype "input"))
      (node (ref "E5") (pin "8") (pinfunction "I0_8") (pintype "input"))
      (node (ref "E8") (pin "8") (pinfunction "O_8") (pintype "output"))
    )
    (net (code "105") (name "/~{READ}") (class "Default")
      (node (ref "E39") (pin "1") (pinfunction "I0_1") (pintype "input"))
      (node (ref "E39") (pin "2") (pinfunction "I1_2") (pintype "input"))
      (node (ref "E39") (pin "4") (pinfunction "I2_4") (pintype "input"))
      (node (ref "E39") (pin "5") (pinfunction "I3_5") (pintype "input"))
      (node (ref "E7") (pin "6") (pinfunction "~{Q}_6") (pintype "output"))
    )
    (net (code "106") (name "/~{SKIP}") (class "Default")
      (node (ref "E20") (pin "1") (pinfunction "O_1") (pintype "open_collector"))
      (node (ref "E20") (pin "10") (pinfunction "O_10") (pintype "open_collector"))
      (node (ref "E20") (pin "13") (pinfunction "O_13") (pintype "open_collector"))
      (node (ref "E20") (pin "4") (pinfunction "O_4") (pintype "open_collector"))
      (node (ref "EDGE") (pin "CS1") (pinfunction "1_CS1") (pintype "bidirectional"))
    )
    (net (code "107") (name "/~{TCLR}") (class "Default")
      (node (ref "E1") (pin "4") (pinfunction "O_4") (pintype "output"))
      (node (ref "E7") (pin "13") (pinfunction "CLR_13") (pintype "input"))
      (node (ref "EDGE") (pin "BA1") (pinfunction "1_BA1") (pintype "bidirectional"))
    )
    (net (code "108") (name "/~{TP3}") (class "Default")
      (node (ref "E1") (pin "11") (pinfunction "I0_11") (pintype "input"))
      (node (ref "E1") (pin "3") (pinfunction "I1_3") (pintype "input"))
      (node (ref "E25") (pin "11") (pinfunction "I0_11") (pintype "input"))
      (node (ref "E25") (pin "12") (pinfunction "I1_12") (pintype "input"))
      (node (ref "E25") (pin "14") (pinfunction "O_14") (pintype "output"))
    )
    (net (code "109") (name "/~{TRANSIT}") (class "Default")
      (node (ref "E35") (pin "6") (pinfunction "I1_6") (pintype "input"))
      (node (ref "E6") (pin "12") (pinfunction "I0_12") (pintype "input"))
      (node (ref "E6") (pin "13") (pinfunction "I1_13") (pintype "input"))
      (node (ref "E7") (pin "8") (pinfunction "~{Q}_8") (pintype "output"))
    )
    (net (code "110") (name "/~{ZONE1}") (class "Default")
      (node (ref "E10") (pin "1") (pinfunction "~{Q1}_1") (pintype "output"))
      (node (ref "E22") (pin "9") (pinfunction "I0_9") (pintype "input"))
      (node (ref "E26") (pin "11") (pinfunction "I2_11") (pintype "input"))
      (node (ref "E26") (pin "2") (pinfunction "I1_2") (pintype "input"))
    )
    (net (code "111") (name "/~{ZONE2}") (class "Default")
      (node (ref "E18") (pin "8") (pinfunction "~{Q4}_8") (pintype "output"))
      (node (ref "E22") (pin "5") (pinfunction "I3_5") (pintype "input"))
      (node (ref "E26") (pin "13") (pinfunction "I2_13") (pintype "input"))
      (node (ref "E34") (pin "1") (pinfunction "I0_1") (pintype "input"))
    )
    (net (code "112") (name "/~{ZONE3}") (class "Default")
      (node (ref "E18") (pin "11") (pinfunction "~{Q3}_11") (pintype "output"))
      (node (ref "E22") (pin "12") (pinfunction "I2_12") (pintype "input"))
      (node (ref "E22") (pin "2") (pinfunction "I1_2") (pintype "input"))
      (node (ref "E26") (pin "1") (pinfunction "I0_1") (pintype "input"))
    )
    (net (code "113") (name "/~{ZONE4}") (class "Default")
      (node (ref "E18") (pin "14") (pinfunction "~{Q2}_14") (pintype "output"))
      (node (ref "E26") (pin "10") (pinfunction "I1_10") (pintype "input"))
      (node (ref "E34") (pin "12") (pinfunction "I2_12") (pintype "input"))
      (node (ref "E34") (pin "2") (pinfunction "I1_2") (pintype "input"))
    )
    (net (code "114") (name "/~{ZONE5}") (class "Default")
      (node (ref "E18") (pin "1") (pinfunction "~{Q1}_1") (pintype "output"))
      (node (ref "E22") (pin "13") (pinfunction "I3_13") (pintype "input"))
      (node (ref "E26") (pin "9") (pinfunction "I0_9") (pintype "input"))
      (node (ref "E34") (pin "13") (pinfunction "I3_13") (pintype "input"))
    )
    (net (code "115") (name "/~{ZONE6}") (class "Default")
      (node (ref "E22") (pin "1") (pinfunction "I0_1") (pintype "input"))
      (node (ref "E34") (pin "10") (pinfunction "I1_10") (pintype "input"))
      (node (ref "E34") (pin "4") (pinfunction "I2_4") (pintype "input"))
      (node (ref "E34") (pin "5") (pinfunction "I3_5") (pintype "input"))
      (node (ref "E38") (pin "8") (pinfunction "~{Q4}_8") (pintype "output"))
    )
    (net (code "116") (name "/~{ZONE7}") (class "Default")
      (node (ref "E22") (pin "10") (pinfunction "I1_10") (pintype "input"))
      (node (ref "E22") (pin "4") (pinfunction "I2_4") (pintype "input"))
      (node (ref "E34") (pin "9") (pinfunction "I0_9") (pintype "input"))
      (node (ref "E38") (pin "11") (pinfunction "~{Q3}_11") (pintype "output"))
    )
    (net (code "117") (name "/~{ZONE8}") (class "Default")
      (node (ref "E38") (pin "14") (pinfunction "~{Q2}_14") (pintype "output"))
      (node (ref "E42") (pin "10") (pinfunction "I1_10") (pintype "input"))
    )
    (net (code "118") (name "/~{ZONE9}") (class "Default")
      (node (ref "E38") (pin "1") (pinfunction "~{Q1}_1") (pintype "output"))
      (node (ref "E42") (pin "5") (pinfunction "I1_5") (pintype "input"))
      (node (ref "E42") (pin "9") (pinfunction "I0_9") (pintype "input"))
    )
    (net (code "119") (name "/~{ZONE10}") (class "Default")
      (node (ref "E10") (pin "14") (pinfunction "~{Q2}_14") (pintype "output"))
      (node (ref "E6") (pin "1") (pinfunction "I0_1") (pintype "input"))
    )
    (net (code "120") (name "/~{ZONE11}") (class "Default")
      (node (ref "E10") (pin "11") (pinfunction "~{Q3}_11") (pintype "output"))
      (node (ref "E6") (pin "5") (pinfunction "I1_5") (pintype "input"))
    )
    (net (code "121") (name "/~{ZONE12}") (class "Default")
      (node (ref "E10") (pin "8") (pinfunction "~{Q4}_8") (pintype "output"))
      (node (ref "E6") (pin "2") (pinfunction "I1_2") (pintype "input"))
      (node (ref "E6") (pin "4") (pinfunction "I0_4") (pintype "input"))
    )
    (net (code "122") (name "GND") (class "Default")
      (node (ref "C1") (pin "2") (pinfunction "2_2") (pintype "passive"))
      (node (ref "C10") (pin "2") (pinfunction "2_2") (pintype "passive"))
      (node (ref "C11") (pin "2") (pinfunction "2_2") (pintype "passive"))
      (node (ref "C12") (pin "2") (pinfunction "2_2") (pintype "passive"))
      (node (ref "C13") (pin "2") (pinfunction "2_2") (pintype "passive"))
      (node (ref "C14") (pin "2") (pinfunction "2_2") (pintype "passive"))
      (node (ref "C15") (pin "2") (pinfunction "2_2") (pintype "passive"))
      (node (ref "C16") (pin "2") (pinfunction "2_2") (pintype "passive"))
      (node (ref "C17") (pin "2") (pinfunction "2_2") (pintype "passive"))
      (node (ref "C18") (pin "2") (pinfunction "2_2") (pintype "passive"))
      (node (ref "C19") (pin "2") (pinfunction "2_2") (pintype "passive"))
      (node (ref "C2") (pin "2") (pinfunction "2_2") (pintype "passive"))
      (node (ref "C20") (pin "2") (pinfunction "2_2") (pintype "passive"))
      (node (ref "C21") (pin "2") (pinfunction "2_2") (pintype "passive"))
      (node (ref "C22") (pin "2") (pinfunction "2_2") (pintype "passive"))
      (node (ref "C23") (pin "2") (pinfunction "2_2") (pintype "passive"))
      (node (ref "C24") (pin "2") (pinfunction "2_2") (pintype "passive"))
      (node (ref "C25") (pin "2") (pinfunction "2_2") (pintype "passive"))
      (node (ref "C26") (pin "2") (pinfunction "2_2") (pintype "passive"))
      (node (ref "C27") (pin "2") (pinfunction "2_2") (pintype "passive"))
      (node (ref "C28") (pin "2") (pinfunction "2_2") (pintype "passive"))
      (node (ref "C29") (pin "2") (pinfunction "2_2") (pintype "passive"))
      (node (ref "C3") (pin "2") (pinfunction "2_2") (pintype "passive"))
      (node (ref "C30") (pin "2") (pinfunction "2_2") (pintype "passive"))
      (node (ref "C31") (pin "2") (pinfunction "2_2") (pintype "passive"))
      (node (ref "C32") (pin "2") (pinfunction "2_2") (pintype "passive"))
      (node (ref "C33") (pin "2") (pinfunction "2_2") (pintype "passive"))
      (node (ref "C34") (pin "2") (pinfunction "2_2") (pintype "passive"))
      (node (ref "C35") (pin "2") (pinfunction "2_2") (pintype "passive"))
      (node (ref "C36") (pin "2") (pinfunction "2_2") (pintype "passive"))
      (node (ref "C37") (pin "2") (pinfunction "2_2") (pintype "passive"))
      (node (ref "C38") (pin "2") (pinfunction "2_2") (pintype "passive"))
      (node (ref "C39") (pin "2") (pinfunction "2_2") (pintype "passive"))
      (node (ref "C4") (pin "2") (pinfunction "2_2") (pintype "passive"))
      (node (ref "C40") (pin "2") (pinfunction "2_2") (pintype "passive"))
      (node (ref "C41") (pin "2") (pinfunction "2_2") (pintype "passive"))
      (node (ref "C42") (pin "2") (pinfunction "2_2") (pintype "passive"))
      (node (ref "C43") (pin "2") (pinfunction "2_2") (pintype "passive"))
      (node (ref "C44") (pin "2") (pinfunction "2_2") (pintype "passive"))
      (node (ref "C45") (pin "-") (pinfunction "-_-") (pintype "passive"))
      (node (ref "C46") (pin "-") (pinfunction "-_-") (pintype "passive"))
      (node (ref "C47") (pin "-") (pinfunction "-_-") (pintype "passive"))
      (node (ref "C5") (pin "2") (pinfunction "2_2") (pintype "passive"))
      (node (ref "C50") (pin "2") (pinfunction "2_2") (pintype "passive"))
      (node (ref "C51") (pin "2") (pinfunction "2_2") (pintype "passive"))
      (node (ref "C52") (pin "2") (pinfunction "2_2") (pintype "passive"))
      (node (ref "C6") (pin "2") (pinfunction "2_2") (pintype "passive"))
      (node (ref "C7") (pin "2") (pinfunction "2_2") (pintype "passive"))
      (node (ref "C8") (pin "2") (pinfunction "2_2") (pintype "passive"))
      (node (ref "C9") (pin "2") (pinfunction "2_2") (pintype "passive"))
      (node (ref "D1") (pin "A") (pinfunction "A_A") (pintype "passive"))
      (node (ref "DL1") (pin "2") (pinfunction "2_2") (pintype "passive"))
      (node (ref "E25") (pin "6") (pinfunction "I0_6") (pintype "input"))
      (node (ref "E25") (pin "9") (pinfunction "I0_9") (pintype "input"))
      (node (ref "E29") (pin "10") (pinfunction "I1_10") (pintype "input"))
      (node (ref "E32") (pin "1") (pinfunction "P$1_1") (pintype "input"))
      (node (ref "E32") (pin "2") (pinfunction "P$2_2") (pintype "input"))
      (node (ref "E40") (pin "12") (pinfunction "I1_12") (pintype "input"))
      (node (ref "E40") (pin "5") (pinfunction "I1_5") (pintype "input"))
      (node (ref "E43") (pin "1") (pinfunction "P$1_1") (pintype "input"))
      (node (ref "E43") (pin "2") (pinfunction "P$2_2") (pintype "input"))
      (node (ref "E7") (pin "11") (pinfunction "CLK_11") (pintype "input"))
      (node (ref "E7") (pin "12") (pinfunction "D_12") (pintype "input"))
      (node (ref "E7") (pin "2") (pinfunction "D_2") (pintype "input"))
      (node (ref "EDGE") (pin "AC2") (pinfunction "1_AC2") (pintype "bidirectional"))
      (node (ref "EDGE") (pin "AF1") (pinfunction "1_AF1") (pintype "bidirectional"))
      (node (ref "EDGE") (pin "AF2") (pinfunction "1_AF2") (pintype "bidirectional"))
      (node (ref "EDGE") (pin "AN1") (pinfunction "1_AN1") (pintype "bidirectional"))
      (node (ref "EDGE") (pin "AN2") (pinfunction "1_AN2") (pintype "bidirectional"))
      (node (ref "EDGE") (pin "AT1") (pinfunction "1_AT1") (pintype "bidirectional"))
      (node (ref "EDGE") (pin "AT2") (pinfunction "1_AT2") (pintype "bidirectional"))
      (node (ref "EDGE") (pin "BC1") (pinfunction "1_BC1") (pintype "bidirectional"))
      (node (ref "EDGE") (pin "BC2") (pinfunction "1_BC2") (pintype "bidirectional"))
      (node (ref "EDGE") (pin "BF1") (pinfunction "1_BF1") (pintype "bidirectional"))
      (node (ref "EDGE") (pin "BF2") (pinfunction "1_BF2") (pintype "bidirectional"))
      (node (ref "EDGE") (pin "BN1") (pinfunction "1_BN1") (pintype "bidirectional"))
      (node (ref "EDGE") (pin "BN2") (pinfunction "1_BN2") (pintype "bidirectional"))
      (node (ref "EDGE") (pin "BT1") (pinfunction "1_BT1") (pintype "bidirectional"))
      (node (ref "EDGE") (pin "BT2") (pinfunction "1_BT2") (pintype "bidirectional"))
      (node (ref "EDGE") (pin "CC1") (pinfunction "1_CC1") (pintype "bidirectional"))
      (node (ref "EDGE") (pin "CC2") (pinfunction "1_CC2") (pintype "bidirectional"))
      (node (ref "EDGE") (pin "CF1") (pinfunction "1_CF1") (pintype "bidirectional"))
      (node (ref "EDGE") (pin "CF2") (pinfunction "1_CF2") (pintype "bidirectional"))
      (node (ref "EDGE") (pin "CN1") (pinfunction "1_CN1") (pintype "bidirectional"))
      (node (ref "EDGE") (pin "CN2") (pinfunction "1_CN2") (pintype "bidirectional"))
      (node (ref "EDGE") (pin "CT1") (pinfunction "1_CT1") (pintype "bidirectional"))
      (node (ref "EDGE") (pin "CT2") (pinfunction "1_CT2") (pintype "bidirectional"))
      (node (ref "EDGE") (pin "DC1") (pinfunction "1_DC1") (pintype "bidirectional"))
      (node (ref "EDGE") (pin "DC2") (pinfunction "1_DC2") (pintype "bidirectional"))
      (node (ref "EDGE") (pin "DF1") (pinfunction "1_DF1") (pintype "bidirectional"))
      (node (ref "EDGE") (pin "DF2") (pinfunction "1_DF2") (pintype "bidirectional"))
      (node (ref "EDGE") (pin "DN1") (pinfunction "1_DN1") (pintype "bidirectional"))
      (node (ref "EDGE") (pin "DN2") (pinfunction "1_DN2") (pintype "bidirectional"))
      (node (ref "EDGE") (pin "DT1") (pinfunction "1_DT1") (pintype "bidirectional"))
      (node (ref "EDGE") (pin "DT2") (pinfunction "1_DT2") (pintype "bidirectional"))
      (node (ref "R13") (pin "1") (pinfunction "1_1") (pintype "passive"))
      (node (ref "R4") (pin "1") (pinfunction "1_1") (pintype "passive"))
      (node (ref "R7") (pin "1") (pinfunction "1_1") (pintype "passive"))
    )
    (net (code "123") (name "Net-(E1A-O)") (class "Default")
      (node (ref "E1") (pin "1") (pinfunction "O_1") (pintype "output"))
      (node (ref "E1") (pin "5") (pinfunction "I0_5") (pintype "input"))
    )
    (net (code "124") (name "Net-(E1B-I1)") (class "Default")
      (node (ref "E1") (pin "6") (pinfunction "I1_6") (pintype "input"))
      (node (ref "E35") (pin "8") (pinfunction "I0_8") (pintype "input"))
      (node (ref "E36") (pin "12") (pinfunction "O_12") (pintype "output"))
    )
    (net (code "125") (name "Net-(E6C-O)") (class "Default")
      (node (ref "E6") (pin "8") (pinfunction "O_8") (pintype "output"))
      (node (ref "E8") (pin "1") (pinfunction "I_1") (pintype "input"))
    )
    (net (code "126") (name "Net-(E11A-CLR)") (class "Default")
      (node (ref "E11") (pin "1") (pinfunction "CLR_1") (pintype "input"))
      (node (ref "E8") (pin "2") (pinfunction "O_2") (pintype "output"))
    )
    (net (code "127") (name "Net-(E11A-D)") (class "Default")
      (node (ref "E11") (pin "12") (pinfunction "D_12") (pintype "input"))
      (node (ref "E11") (pin "2") (pinfunction "D_2") (pintype "input"))
      (node (ref "R5") (pin "1") (pinfunction "1_1") (pintype "passive"))
    )
    (net (code "128") (name "Net-(E11B-CLK)") (class "Default")
      (node (ref "E11") (pin "11") (pinfunction "CLK_11") (pintype "input"))
      (node (ref "E36") (pin "8") (pinfunction "O_8") (pintype "output"))
    )
    (net (code "129") (name "Net-(E11B-CLR)") (class "Default")
      (node (ref "E11") (pin "13") (pinfunction "CLR_13") (pintype "input"))
      (node (ref "E8") (pin "4") (pinfunction "O_4") (pintype "output"))
    )
    (net (code "130") (name "Net-(E19A-I1)") (class "Default")
      (node (ref "E19") (pin "10") (pinfunction "I1_10") (pintype "input"))
      (node (ref "E42") (pin "11") (pinfunction "O_11") (pintype "output"))
    )
    (net (code "131") (name "Net-(E19A-O)") (class "Default")
      (node (ref "E19") (pin "8") (pinfunction "O_8") (pintype "output"))
      (node (ref "E36") (pin "5") (pinfunction "I_5") (pintype "input"))
    )
    (net (code "132") (name "Net-(E19B-I2)") (class "Default")
      (node (ref "DL1") (pin "3") (pinfunction "3_3") (pintype "passive"))
      (node (ref "E19") (pin "3") (pinfunction "I2_3") (pintype "input"))
      (node (ref "E8") (pin "5") (pinfunction "I_5") (pintype "input"))
      (node (ref "R3") (pin "1") (pinfunction "1_1") (pintype "passive"))
      (node (ref "R4") (pin "2") (pinfunction "2_2") (pintype "passive"))
    )
    (net (code "133") (name "Net-(E19B-I3)") (class "Default")
      (node (ref "E19") (pin "4") (pinfunction "I3_4") (pintype "input"))
      (node (ref "E8") (pin "6") (pinfunction "O_6") (pintype "output"))
    )
    (net (code "134") (name "Net-(E19B-O)") (class "Default")
      (node (ref "E19") (pin "6") (pinfunction "O_6") (pintype "output"))
      (node (ref "E7") (pin "10") (pinfunction "PRE_10") (pintype "input"))
    )
    (net (code "135") (name "Net-(E20B-I0)") (class "Default")
      (node (ref "E20") (pin "5") (pinfunction "I0_5") (pintype "input"))
      (node (ref "E8") (pin "10") (pinfunction "O_10") (pintype "output"))
    )
    (net (code "136") (name "Net-(E20B-I1)") (class "Default")
      (node (ref "E20") (pin "6") (pinfunction "I1_6") (pintype "input"))
      (node (ref "E36") (pin "6") (pinfunction "O_6") (pintype "output"))
    )
    (net (code "137") (name "Net-(E20C-I1)") (class "Default")
      (node (ref "E20") (pin "9") (pinfunction "I1_9") (pintype "input"))
      (node (ref "E35") (pin "1") (pinfunction "O_1") (pintype "output"))
    )
    (net (code "138") (name "Net-(E20D-I1)") (class "Default")
      (node (ref "E20") (pin "12") (pinfunction "I1_12") (pintype "input"))
      (node (ref "E8") (pin "12") (pinfunction "O_12") (pintype "output"))
    )
    (net (code "139") (name "Net-(E21C-I0)") (class "Default")
      (node (ref "E21") (pin "8") (pinfunction "I0_8") (pintype "input"))
      (node (ref "E6") (pin "6") (pinfunction "O_6") (pintype "output"))
    )
    (net (code "140") (name "Net-(E21D-I1)") (class "Default")
      (node (ref "E21") (pin "12") (pinfunction "I1_12") (pintype "input"))
      (node (ref "E6") (pin "3") (pinfunction "O_3") (pintype "output"))
    )
    (net (code "141") (name "Net-(E23A-D)") (class "Default")
      (node (ref "E23") (pin "2") (pinfunction "D_2") (pintype "input"))
      (node (ref "E29") (pin "3") (pinfunction "O_3") (pintype "output"))
    )
    (net (code "142") (name "Net-(E23B-D)") (class "Default")
      (node (ref "E23") (pin "12") (pinfunction "D_12") (pintype "input"))
      (node (ref "E29") (pin "2") (pinfunction "O_2") (pintype "output"))
    )
    (net (code "143") (name "Net-(E24A-I1)") (class "Default")
      (node (ref "E24") (pin "2") (pinfunction "I1_2") (pintype "input"))
      (node (ref "E24") (pin "6") (pinfunction "O_6") (pintype "output"))
    )
    (net (code "144") (name "Net-(E24A-O)") (class "Default")
      (node (ref "E24") (pin "3") (pinfunction "O_3") (pintype "output"))
      (node (ref "E8") (pin "3") (pinfunction "I_3") (pintype "input"))
      (node (ref "EDGE") (pin "DA1") (pinfunction "1_DA1") (pintype "bidirectional"))
    )
    (net (code "145") (name "Net-(E24B-I1)") (class "Default")
      (node (ref "E24") (pin "5") (pinfunction "I1_5") (pintype "input"))
      (node (ref "E24") (pin "8") (pinfunction "O_8") (pintype "output"))
    )
    (net (code "146") (name "Net-(E25A-I0)") (class "Default")
      (node (ref "E25") (pin "2") (pinfunction "O_2") (pintype "output"))
      (node (ref "E25") (pin "4") (pinfunction "I0_4") (pintype "input"))
      (node (ref "E25") (pin "5") (pinfunction "I1_5") (pintype "input"))
    )
    (net (code "147") (name "Net-(E26A-O)") (class "Default")
      (node (ref "E26") (pin "12") (pinfunction "O_12") (pintype "output"))
      (node (ref "E30") (pin "4") (pinfunction "I0_4") (pintype "input"))
    )
    (net (code "148") (name "Net-(E26B-I0)") (class "Default")
      (node (ref "E26") (pin "3") (pinfunction "I0_3") (pintype "input"))
      (node (ref "E30") (pin "11") (pinfunction "O_11") (pintype "output"))
    )
    (net (code "149") (name "Net-(E26B-I1)") (class "Default")
      (node (ref "E26") (pin "4") (pinfunction "I1_4") (pintype "input"))
      (node (ref "E30") (pin "8") (pinfunction "O_8") (pintype "output"))
    )
    (net (code "150") (name "Net-(E26B-I2)") (class "Default")
      (node (ref "E26") (pin "5") (pinfunction "I2_5") (pintype "input"))
      (node (ref "E30") (pin "6") (pinfunction "O_6") (pintype "output"))
    )
    (net (code "151") (name "Net-(E26C-O)") (class "Default")
      (node (ref "E26") (pin "8") (pinfunction "O_8") (pintype "output"))
      (node (ref "E30") (pin "13") (pinfunction "I1_13") (pintype "input"))
    )
    (net (code "152") (name "Net-(E27A-O)") (class "Default")
      (node (ref "E27") (pin "12") (pinfunction "O_12") (pintype "output"))
      (node (ref "E7") (pin "4") (pinfunction "PRE_4") (pintype "input"))
    )
    (net (code "153") (name "Net-(E30A-O)") (class "Default")
      (node (ref "E30") (pin "3") (pinfunction "O_3") (pintype "output"))
      (node (ref "E6") (pin "9") (pinfunction "I0_9") (pintype "input"))
    )
    (net (code "154") (name "Net-(E30C-I0)") (class "Default")
      (node (ref "E30") (pin "9") (pinfunction "I0_9") (pintype "input"))
      (node (ref "E34") (pin "6") (pinfunction "O_6") (pintype "output"))
    )
    (net (code "155") (name "Net-(E32A-P$3)") (class "Default")
      (node (ref "E32") (pin "3") (pinfunction "P$3_3") (pintype "input"))
      (node (ref "E32") (pin "4") (pinfunction "P$4_4") (pintype "input"))
      (node (ref "E43") (pin "6") (pinfunction "~{Q}_6") (pintype "output"))
    )
    (net (code "156") (name "Net-(E32A-P$5)") (class "Default")
      (node (ref "C48") (pin "1") (pinfunction "1_1") (pintype "passive"))
      (node (ref "E32") (pin "11") (pinfunction "P$5_11") (pintype "bidirectional"))
    )
    (net (code "157") (name "Net-(E32A-P$6)") (class "Default")
      (node (ref "C48") (pin "2") (pinfunction "2_2") (pintype "passive"))
      (node (ref "E32") (pin "13") (pinfunction "P$6_13") (pintype "bidirectional"))
      (node (ref "R10") (pin "1") (pinfunction "1_1") (pintype "passive"))
    )
    (net (code "158") (name "Net-(E32A-~{Q})") (class "Default")
      (node (ref "E32") (pin "6") (pinfunction "~{Q}_6") (pintype "output"))
      (node (ref "E39") (pin "10") (pinfunction "I1_10") (pintype "input"))
      (node (ref "E39") (pin "12") (pinfunction "I2_12") (pintype "input"))
      (node (ref "E39") (pin "13") (pinfunction "I3_13") (pintype "input"))
      (node (ref "E39") (pin "9") (pinfunction "I0_9") (pintype "input"))
    )
    (net (code "159") (name "Net-(E35B-O)") (class "Default")
      (node (ref "E35") (pin "4") (pinfunction "O_4") (pintype "output"))
      (node (ref "E5") (pin "12") (pinfunction "I1_12") (pintype "input"))
      (node (ref "E5") (pin "9") (pinfunction "I1_9") (pintype "input"))
    )
    (net (code "160") (name "Net-(E35C-O)") (class "Default")
      (node (ref "E35") (pin "10") (pinfunction "O_10") (pintype "output"))
      (node (ref "E7") (pin "1") (pinfunction "CLR_1") (pintype "input"))
    )
    (net (code "161") (name "Net-(E40A-I0)") (class "Default")
      (node (ref "E40") (pin "2") (pinfunction "O_2") (pintype "output"))
      (node (ref "E40") (pin "4") (pinfunction "I0_4") (pintype "input"))
    )
    (net (code "162") (name "Net-(E40B-I0)") (class "Default")
      (node (ref "C52") (pin "1") (pinfunction "1_1") (pintype "passive"))
      (node (ref "E40") (pin "6") (pinfunction "I0_6") (pintype "input"))
      (node (ref "E40") (pin "7") (pinfunction "I1_7") (pintype "input"))
      (node (ref "R8") (pin "2") (pinfunction "2_2") (pintype "passive"))
      (node (ref "R9") (pin "1") (pinfunction "1_1") (pintype "passive"))
    )
    (net (code "163") (name "Net-(E40C-I0)") (class "Default")
      (node (ref "E40") (pin "9") (pinfunction "I0_9") (pintype "input"))
      (node (ref "R1") (pin "1") (pinfunction "1_1") (pintype "passive"))
    )
    (net (code "164") (name "Net-(E40C-I1)") (class "Default")
      (node (ref "C51") (pin "1") (pinfunction "1_1") (pintype "passive"))
      (node (ref "E40") (pin "10") (pinfunction "I1_10") (pintype "input"))
      (node (ref "R2") (pin "2") (pinfunction "2_2") (pintype "passive"))
    )
    (net (code "165") (name "Net-(E41A-I0)") (class "Default")
      (node (ref "E41") (pin "2") (pinfunction "I0_2") (pintype "input"))
      (node (ref "E42") (pin "6") (pinfunction "O_6") (pintype "output"))
    )
    (net (code "166") (name "Net-(E41C-I0)") (class "Default")
      (node (ref "E41") (pin "8") (pinfunction "I0_8") (pintype "input"))
      (node (ref "E42") (pin "8") (pinfunction "O_8") (pintype "output"))
    )
    (net (code "167") (name "Net-(E43A-P$5)") (class "Default")
      (node (ref "C49") (pin "1") (pinfunction "1_1") (pintype "passive"))
      (node (ref "E43") (pin "11") (pinfunction "P$5_11") (pintype "bidirectional"))
    )
    (net (code "168") (name "Net-(E43A-P$6)") (class "Default")
      (node (ref "C49") (pin "2") (pinfunction "2_2") (pintype "passive"))
      (node (ref "E43") (pin "13") (pinfunction "P$6_13") (pintype "bidirectional"))
      (node (ref "R11") (pin "1") (pinfunction "1_1") (pintype "passive"))
    )
    (net (code "169") (name "Net-(EDGEP-1)") (class "Default")
      (node (ref "AJ2") (pin "1") (pinfunction "1_1") (pintype "passive"))
      (node (ref "EDGE") (pin "AJ2") (pinfunction "1_AJ2") (pintype "bidirectional"))
    )
    (net (code "170") (name "Net-(EDGER-1)") (class "Default")
      (node (ref "AK2") (pin "1") (pinfunction "1_1") (pintype "passive"))
      (node (ref "EDGE") (pin "AK2") (pinfunction "1_AK2") (pintype "bidirectional"))
    )
    (net (code "171") (name "Net-(EDGET-1)") (class "Default")
      (node (ref "AL2") (pin "1") (pinfunction "1_1") (pintype "passive"))
      (node (ref "EDGE") (pin "AL2") (pinfunction "1_AL2") (pintype "bidirectional"))
    )
    (net (code "172") (name "Net-(J1A-P)") (class "Default")
      (node (ref "J1") (pin "A") (pinfunction "P_A") (pintype "passive"))
      (node (ref "J1") (pin "AA") (pinfunction "P_AA") (pintype "passive"))
      (node (ref "J1") (pin "B") (pinfunction "P_B") (pintype "passive"))
      (node (ref "J1") (pin "C") (pinfunction "P_C") (pintype "passive"))
      (node (ref "J1") (pin "CC") (pinfunction "P_CC") (pintype "passive"))
      (node (ref "J1") (pin "D") (pinfunction "P_D") (pintype "passive"))
      (node (ref "J1") (pin "E") (pinfunction "P_E") (pintype "passive"))
      (node (ref "J1") (pin "EE") (pinfunction "P_EE") (pintype "passive"))
      (node (ref "J1") (pin "F") (pinfunction "P_F") (pintype "passive"))
      (node (ref "J1") (pin "H") (pinfunction "P_H") (pintype "passive"))
      (node (ref "J1") (pin "HH") (pinfunction "P_HH") (pintype "passive"))
      (node (ref "J1") (pin "K") (pinfunction "P_K") (pintype "passive"))
      (node (ref "J1") (pin "KK") (pinfunction "P_KK") (pintype "passive"))
      (node (ref "J1") (pin "M") (pinfunction "P_M") (pintype "passive"))
      (node (ref "J1") (pin "MM") (pinfunction "P_MM") (pintype "passive"))
      (node (ref "J1") (pin "P") (pinfunction "P_P") (pintype "passive"))
      (node (ref "J1") (pin "PP") (pinfunction "P_PP") (pintype "passive"))
      (node (ref "J1") (pin "S") (pinfunction "P_S") (pintype "passive"))
      (node (ref "J1") (pin "SS") (pinfunction "P_SS") (pintype "passive"))
      (node (ref "J1") (pin "U") (pinfunction "P_U") (pintype "passive"))
      (node (ref "J1") (pin "UU") (pinfunction "P_UU") (pintype "passive"))
      (node (ref "J1") (pin "VV") (pinfunction "P_VV") (pintype "passive"))
      (node (ref "J1") (pin "W") (pinfunction "P_W") (pintype "passive"))
      (node (ref "J1") (pin "Y") (pinfunction "P_Y") (pintype "passive"))
      (node (ref "R13") (pin "2") (pinfunction "2_2") (pintype "passive"))
    )
    (net (code "173") (name "VCC") (class "Default")
      (node (ref "C1") (pin "1") (pinfunction "1_1") (pintype "passive"))
      (node (ref "C10") (pin "1") (pinfunction "1_1") (pintype "passive"))
      (node (ref "C11") (pin "1") (pinfunction "1_1") (pintype "passive"))
      (node (ref "C12") (pin "1") (pinfunction "1_1") (pintype "passive"))
      (node (ref "C13") (pin "1") (pinfunction "1_1") (pintype "passive"))
      (node (ref "C14") (pin "1") (pinfunction "1_1") (pintype "passive"))
      (node (ref "C15") (pin "1") (pinfunction "1_1") (pintype "passive"))
      (node (ref "C16") (pin "1") (pinfunction "1_1") (pintype "passive"))
      (node (ref "C17") (pin "1") (pinfunction "1_1") (pintype "passive"))
      (node (ref "C18") (pin "1") (pinfunction "1_1") (pintype "passive"))
      (node (ref "C19") (pin "1") (pinfunction "1_1") (pintype "passive"))
      (node (ref "C2") (pin "1") (pinfunction "1_1") (pintype "passive"))
      (node (ref "C20") (pin "1") (pinfunction "1_1") (pintype "passive"))
      (node (ref "C21") (pin "1") (pinfunction "1_1") (pintype "passive"))
      (node (ref "C22") (pin "1") (pinfunction "1_1") (pintype "passive"))
      (node (ref "C23") (pin "1") (pinfunction "1_1") (pintype "passive"))
      (node (ref "C24") (pin "1") (pinfunction "1_1") (pintype "passive"))
      (node (ref "C25") (pin "1") (pinfunction "1_1") (pintype "passive"))
      (node (ref "C26") (pin "1") (pinfunction "1_1") (pintype "passive"))
      (node (ref "C27") (pin "1") (pinfunction "1_1") (pintype "passive"))
      (node (ref "C28") (pin "1") (pinfunction "1_1") (pintype "passive"))
      (node (ref "C29") (pin "1") (pinfunction "1_1") (pintype "passive"))
      (node (ref "C3") (pin "1") (pinfunction "1_1") (pintype "passive"))
      (node (ref "C30") (pin "1") (pinfunction "1_1") (pintype "passive"))
      (node (ref "C31") (pin "1") (pinfunction "1_1") (pintype "passive"))
      (node (ref "C32") (pin "1") (pinfunction "1_1") (pintype "passive"))
      (node (ref "C33") (pin "1") (pinfunction "1_1") (pintype "passive"))
      (node (ref "C34") (pin "1") (pinfunction "1_1") (pintype "passive"))
      (node (ref "C35") (pin "1") (pinfunction "1_1") (pintype "passive"))
      (node (ref "C36") (pin "1") (pinfunction "1_1") (pintype "passive"))
      (node (ref "C37") (pin "1") (pinfunction "1_1") (pintype "passive"))
      (node (ref "C38") (pin "1") (pinfunction "1_1") (pintype "passive"))
      (node (ref "C39") (pin "1") (pinfunction "1_1") (pintype "passive"))
      (node (ref "C4") (pin "1") (pinfunction "1_1") (pintype "passive"))
      (node (ref "C40") (pin "1") (pinfunction "1_1") (pintype "passive"))
      (node (ref "C41") (pin "1") (pinfunction "1_1") (pintype "passive"))
      (node (ref "C42") (pin "1") (pinfunction "1_1") (pintype "passive"))
      (node (ref "C43") (pin "1") (pinfunction "1_1") (pintype "passive"))
      (node (ref "C45") (pin "+") (pinfunction "+_+") (pintype "passive"))
      (node (ref "C46") (pin "+") (pinfunction "+_+") (pintype "passive"))
      (node (ref "C47") (pin "+") (pinfunction "+_+") (pintype "passive"))
      (node (ref "C5") (pin "1") (pinfunction "1_1") (pintype "passive"))
      (node (ref "C6") (pin "1") (pinfunction "1_1") (pintype "passive"))
      (node (ref "C7") (pin "1") (pinfunction "1_1") (pintype "passive"))
      (node (ref "C8") (pin "1") (pinfunction "1_1") (pintype "passive"))
      (node (ref "C9") (pin "1") (pinfunction "1_1") (pintype "passive"))
      (node (ref "EDGE") (pin "AA2") (pinfunction "1_AA2") (pintype "bidirectional"))
      (node (ref "EDGE") (pin "BA2") (pinfunction "1_BA2") (pintype "bidirectional"))
      (node (ref "EDGE") (pin "CA2") (pinfunction "1_CA2") (pintype "bidirectional"))
      (node (ref "R10") (pin "2") (pinfunction "2_2") (pintype "passive"))
      (node (ref "R11") (pin "2") (pinfunction "2_2") (pintype "passive"))
      (node (ref "R12") (pin "2") (pinfunction "2_2") (pintype "passive"))
      (node (ref "R3") (pin "2") (pinfunction "2_2") (pintype "passive"))
      (node (ref "R5") (pin "2") (pinfunction "2_2") (pintype "passive"))
      (node (ref "R6") (pin "2") (pinfunction "2_2") (pintype "passive"))
    )
    (net (code "174") (name "unconnected-(E2A-0-Pad13)") (class "Default")
      (node (ref "E2") (pin "13") (pinfunction "0_13") (pintype "output"))
    )
    (net (code "175") (name "unconnected-(E2A-3-Pad10)") (class "Default")
      (node (ref "E2") (pin "10") (pinfunction "3_10") (pintype "output"))
    )
    (net (code "176") (name "unconnected-(E2A-8-Pad6)") (class "Default")
      (node (ref "E2") (pin "6") (pinfunction "8_6") (pintype "output"))
    )
    (net (code "177") (name "unconnected-(E2A-9-Pad7)") (class "Default")
      (node (ref "E2") (pin "7") (pinfunction "9_7") (pintype "output"))
    )
    (net (code "178") (name "unconnected-(E3A-0-Pad13)") (class "Default")
      (node (ref "E3") (pin "13") (pinfunction "0_13") (pintype "output"))
    )
    (net (code "179") (name "unconnected-(E3A-3-Pad10)") (class "Default")
      (node (ref "E3") (pin "10") (pinfunction "3_10") (pintype "output"))
    )
    (net (code "180") (name "unconnected-(E3A-6-Pad4)") (class "Default")
      (node (ref "E3") (pin "4") (pinfunction "6_4") (pintype "output"))
    )
    (net (code "181") (name "unconnected-(E3A-8-Pad6)") (class "Default")
      (node (ref "E3") (pin "6") (pinfunction "8_6") (pintype "output"))
    )
    (net (code "182") (name "unconnected-(E3A-9-Pad7)") (class "Default")
      (node (ref "E3") (pin "7") (pinfunction "9_7") (pintype "output"))
    )
    (net (code "183") (name "unconnected-(E7A-Q-Pad5)") (class "Default")
      (node (ref "E7") (pin "5") (pinfunction "Q_5") (pintype "output"))
    )
    (net (code "184") (name "unconnected-(E19A-I5-Pad12)") (class "Default")
      (node (ref "E19") (pin "12") (pinfunction "I5_12") (pintype "passive"))
    )
    (net (code "185") (name "unconnected-(E19A-I6-Pad11)") (class "Default")
      (node (ref "E19") (pin "11") (pinfunction "I6_11") (pintype "passive"))
    )
    (net (code "186") (name "unconnected-(E23A-~{Q}-Pad6)") (class "Default")
      (node (ref "E23") (pin "6") (pinfunction "~{Q}_6") (pintype "output"))
    )
    (net (code "187") (name "unconnected-(E23B-~{Q}-Pad8)") (class "Default")
      (node (ref "E23") (pin "8") (pinfunction "~{Q}_8") (pintype "output"))
    )
    (net (code "188") (name "unconnected-(E32A-Q-Pad8)") (class "Default")
      (node (ref "E32") (pin "8") (pinfunction "Q_8") (pintype "output"))
    )
    (net (code "189") (name "unconnected-(E43A-Q-Pad8)") (class "Default")
      (node (ref "E43") (pin "8") (pinfunction "Q_8") (pintype "output"))
    )
  )
)
